# SP-PC-V3_0.net
KiCad netlist of a schematic drawn in EAGLE
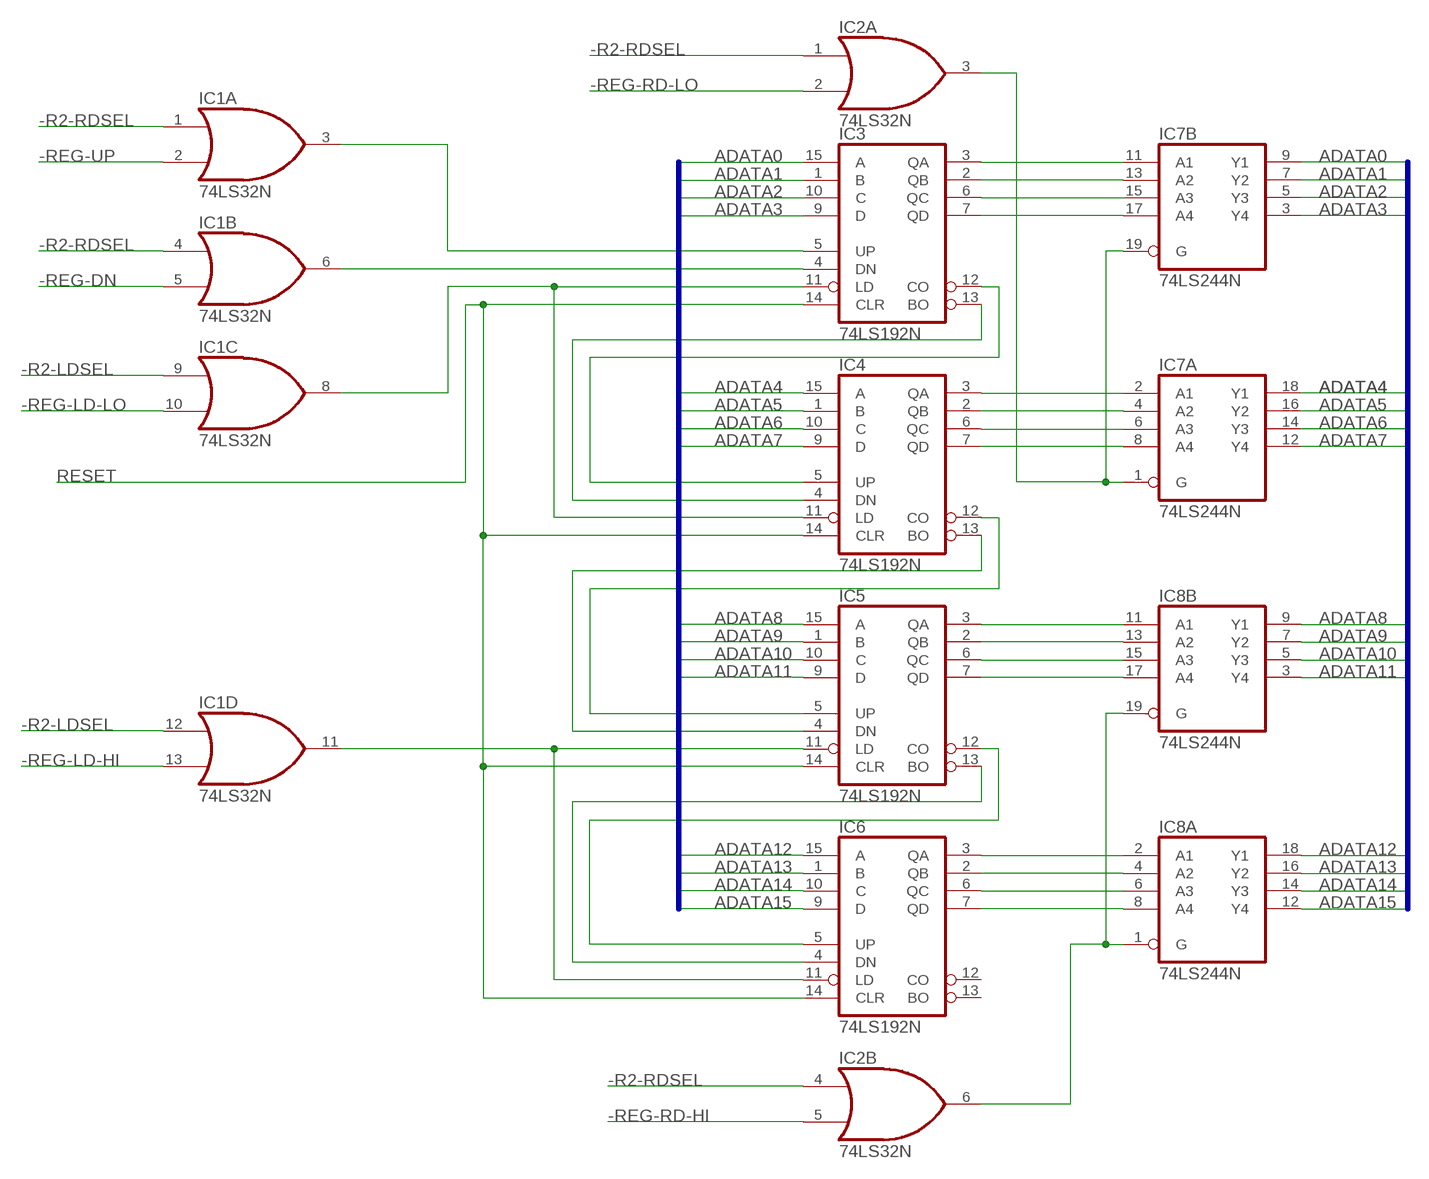
[diagram p0: schematic, sheet 1]
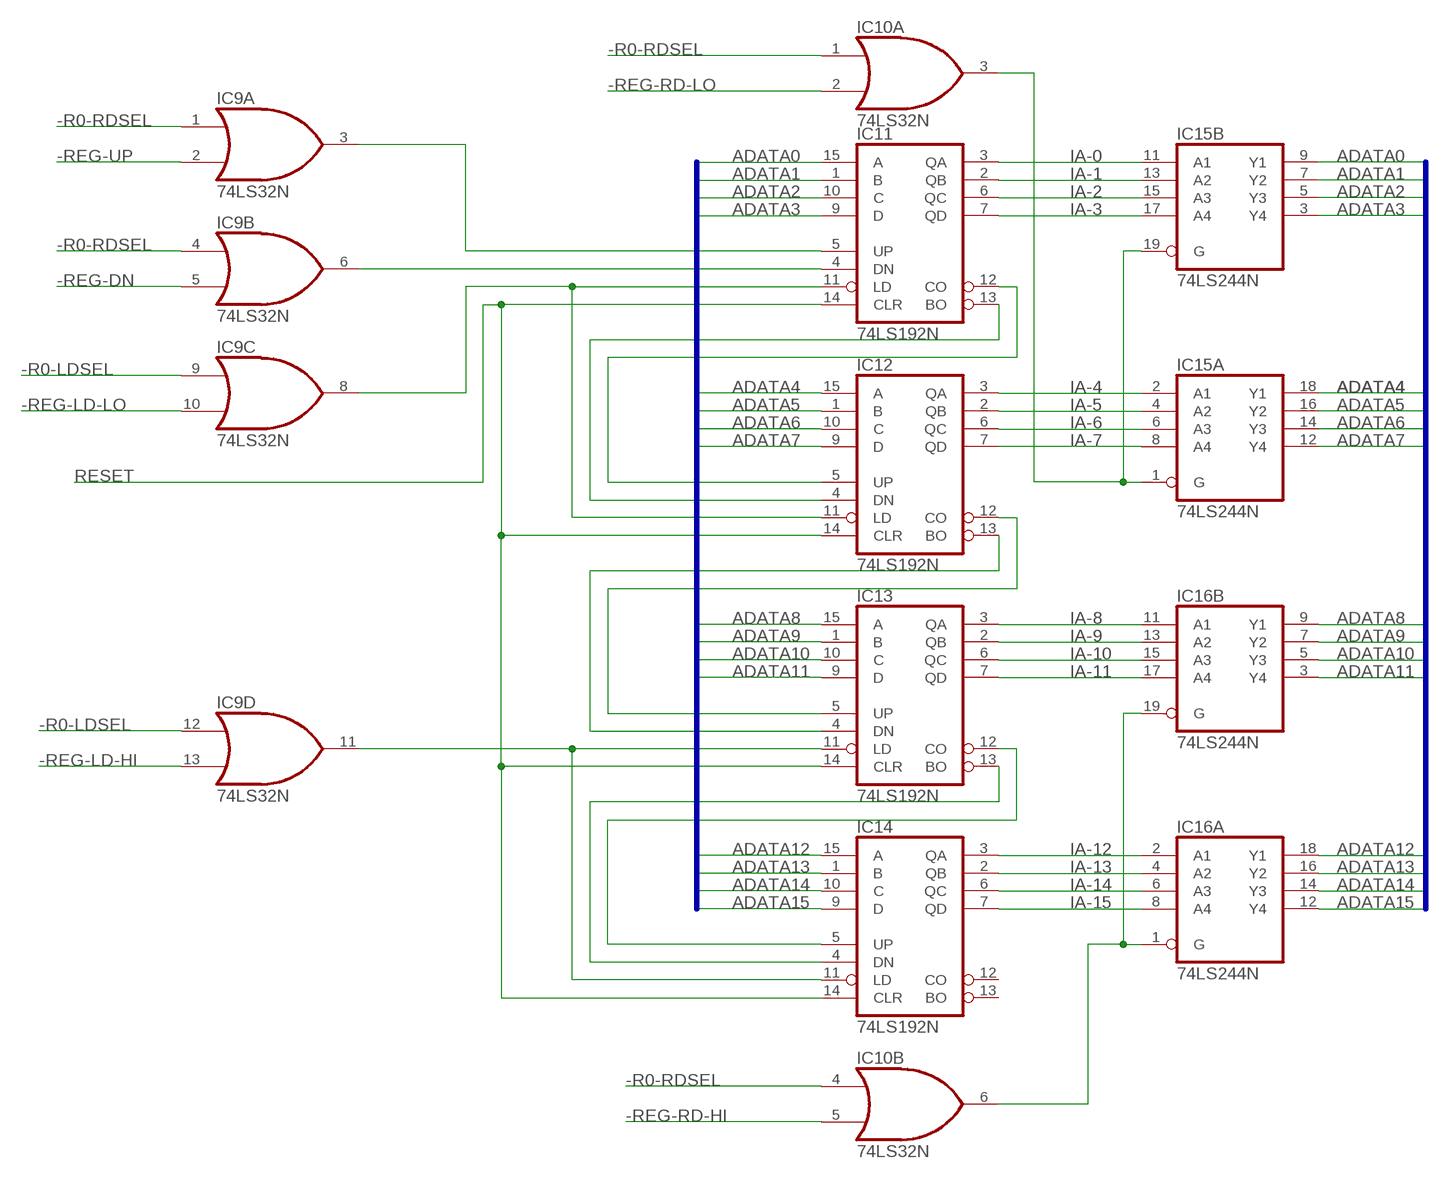
[diagram p1: schematic, sheet 2]
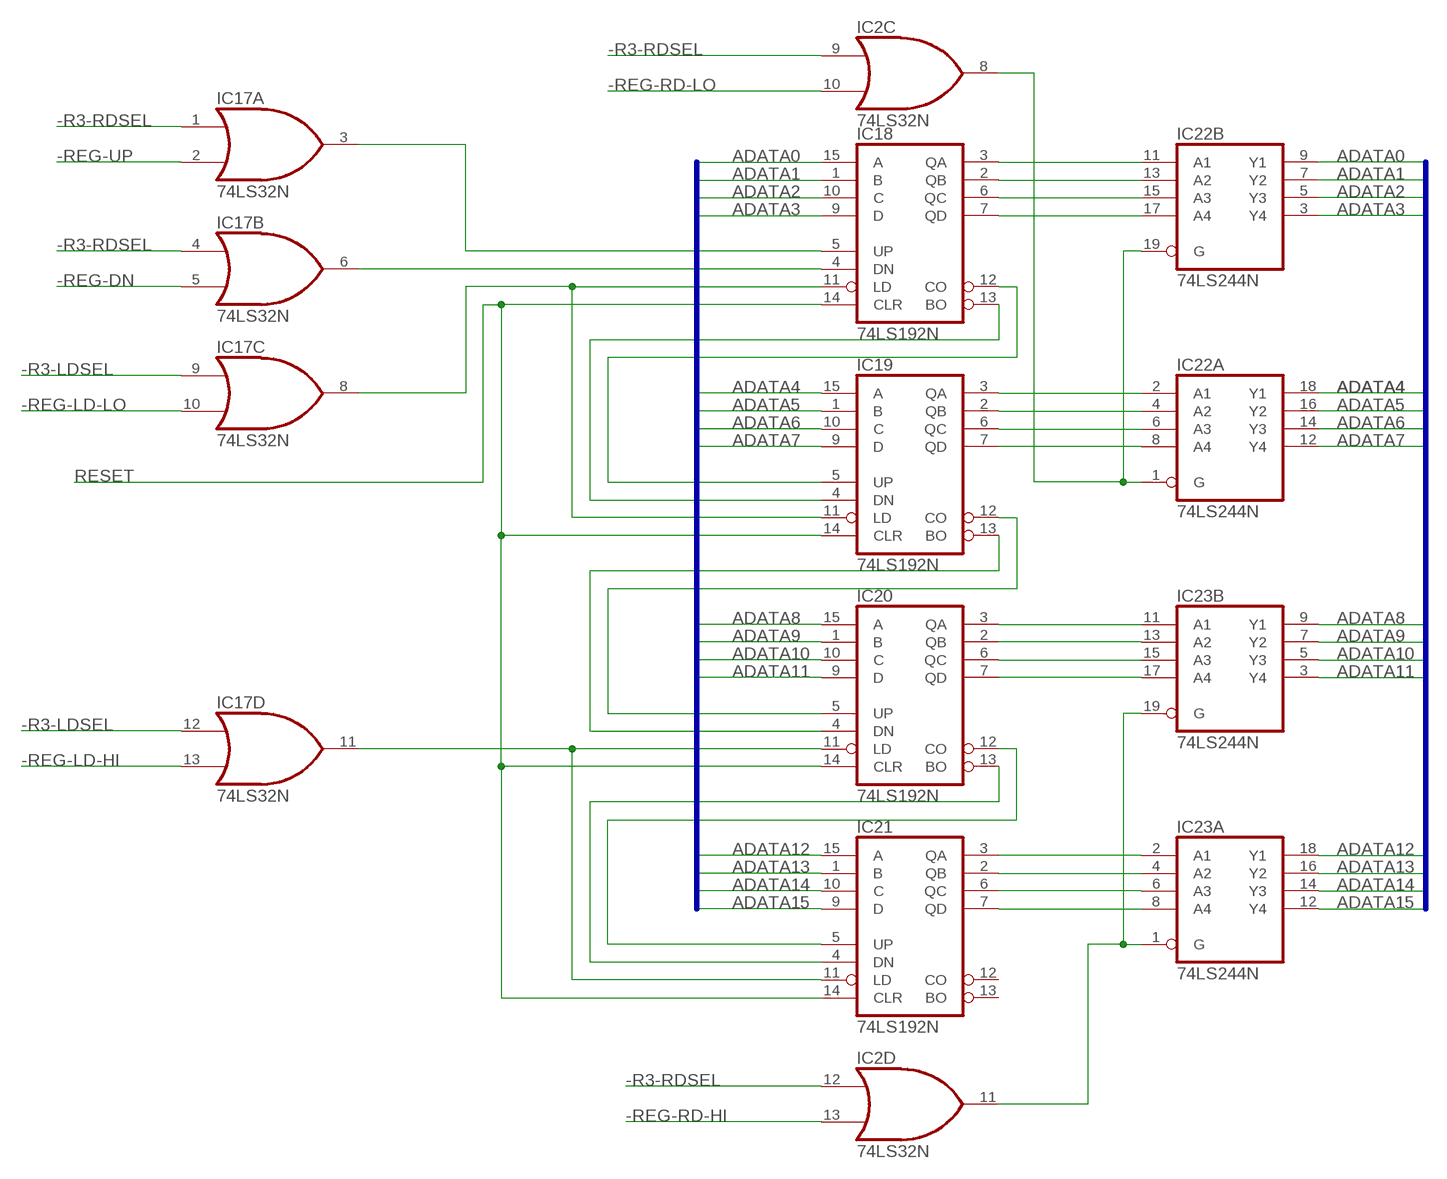
[diagram p2: schematic, sheet 3]
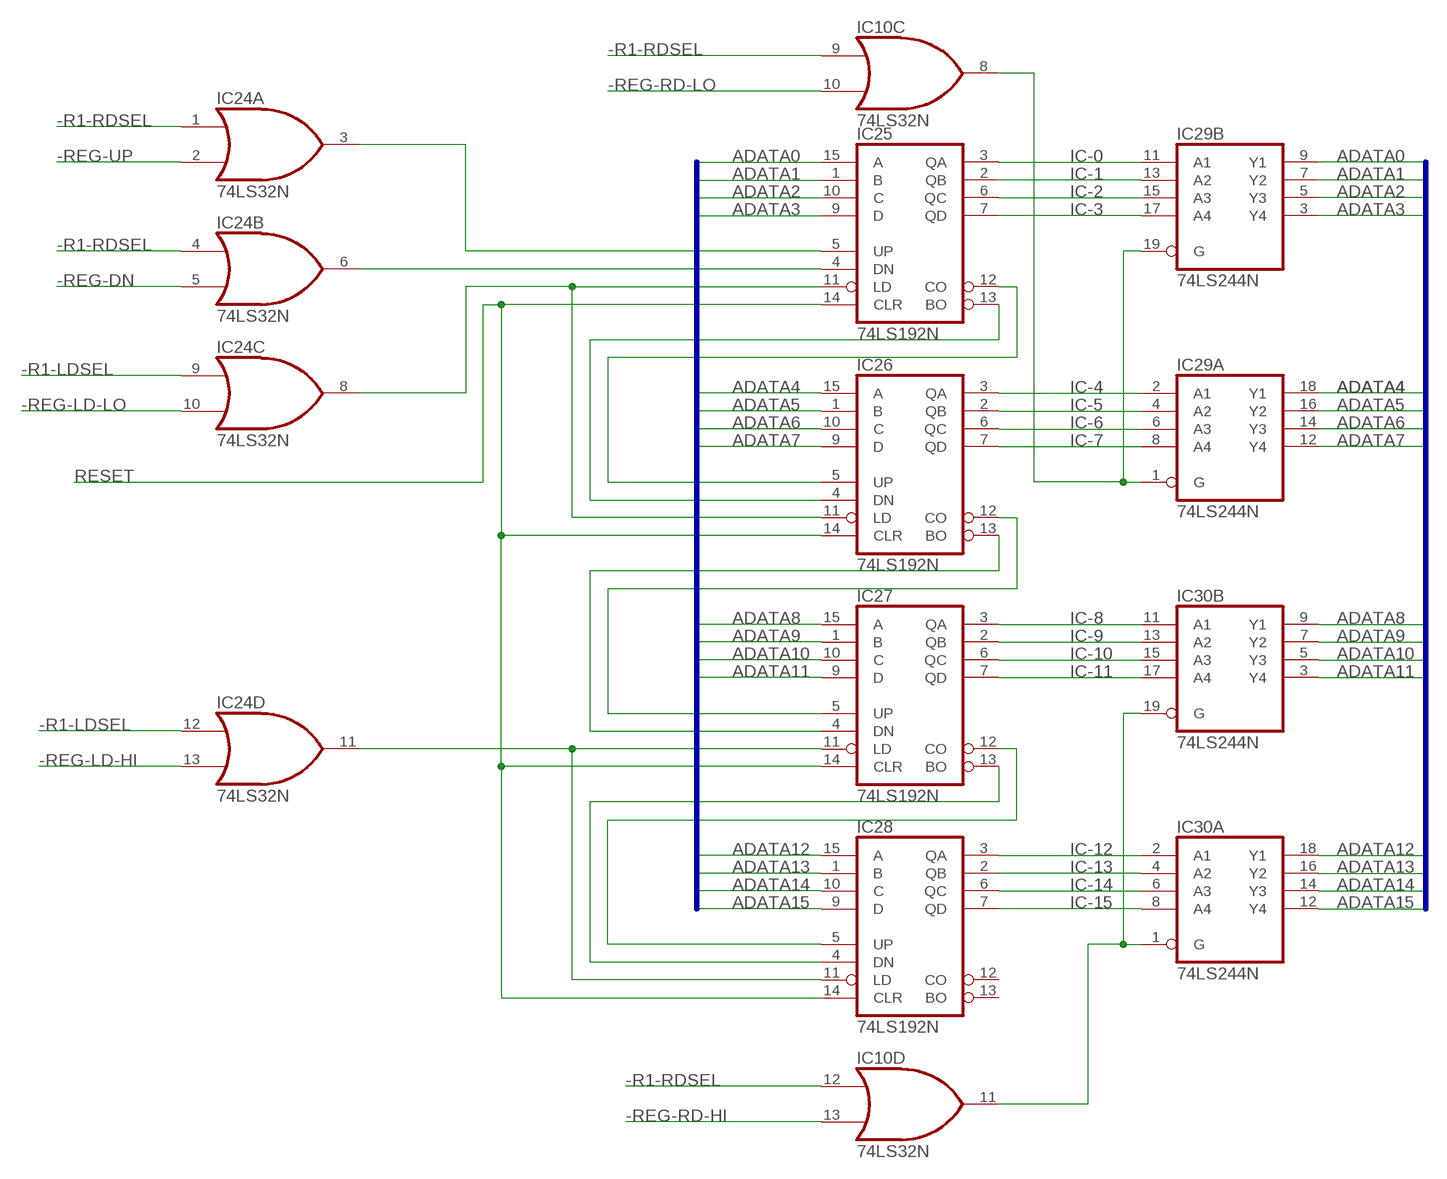
[diagram p3: schematic, sheet 4]
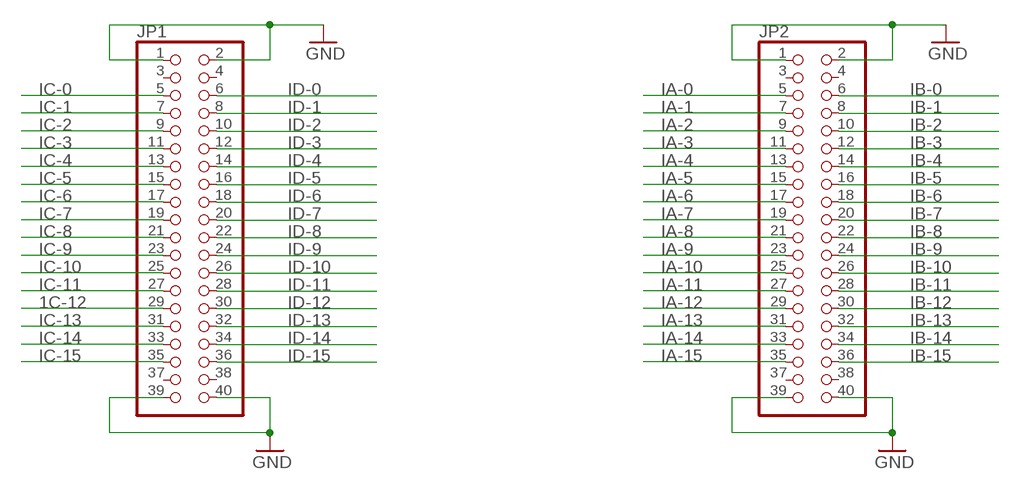
[diagram p4: schematic, sheet 5]
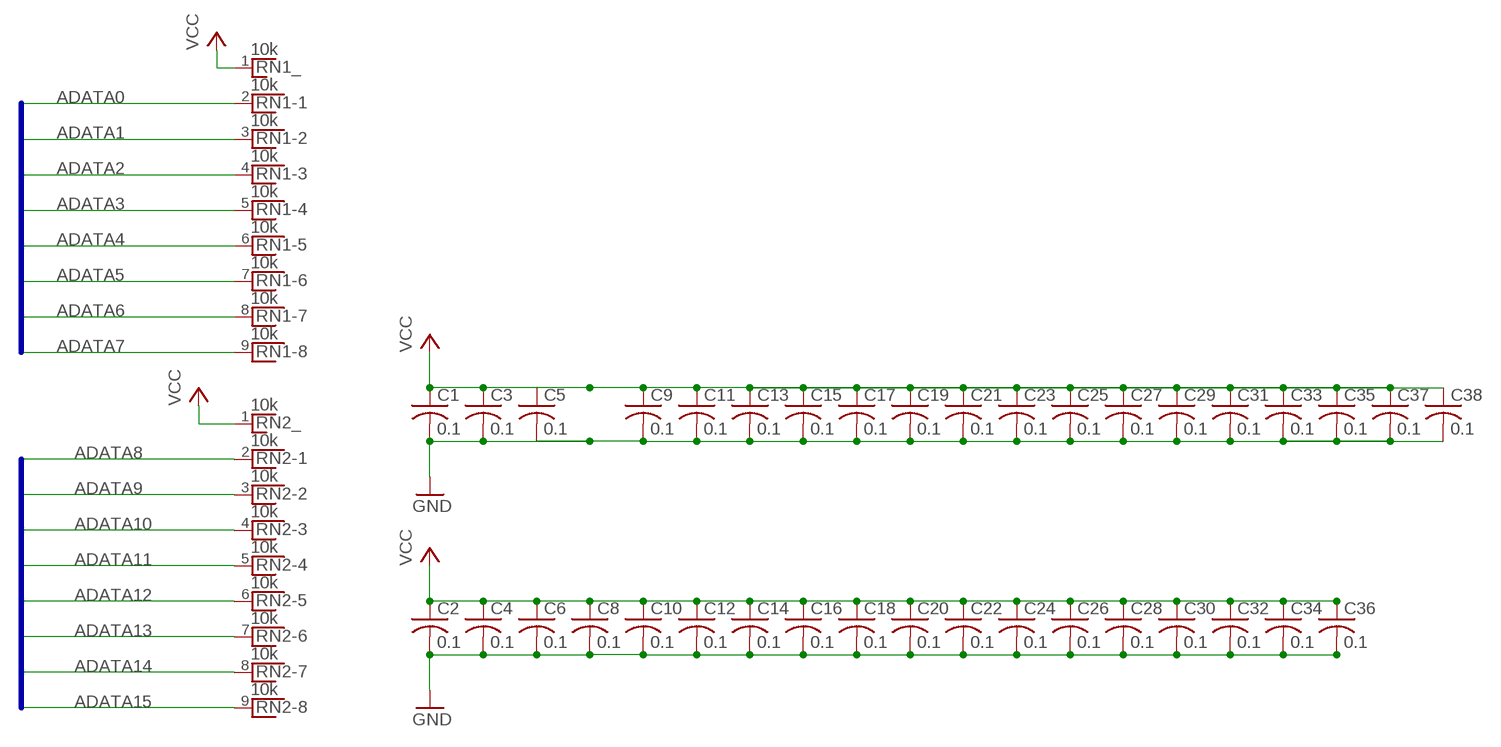
[diagram p5: schematic, sheet 6]
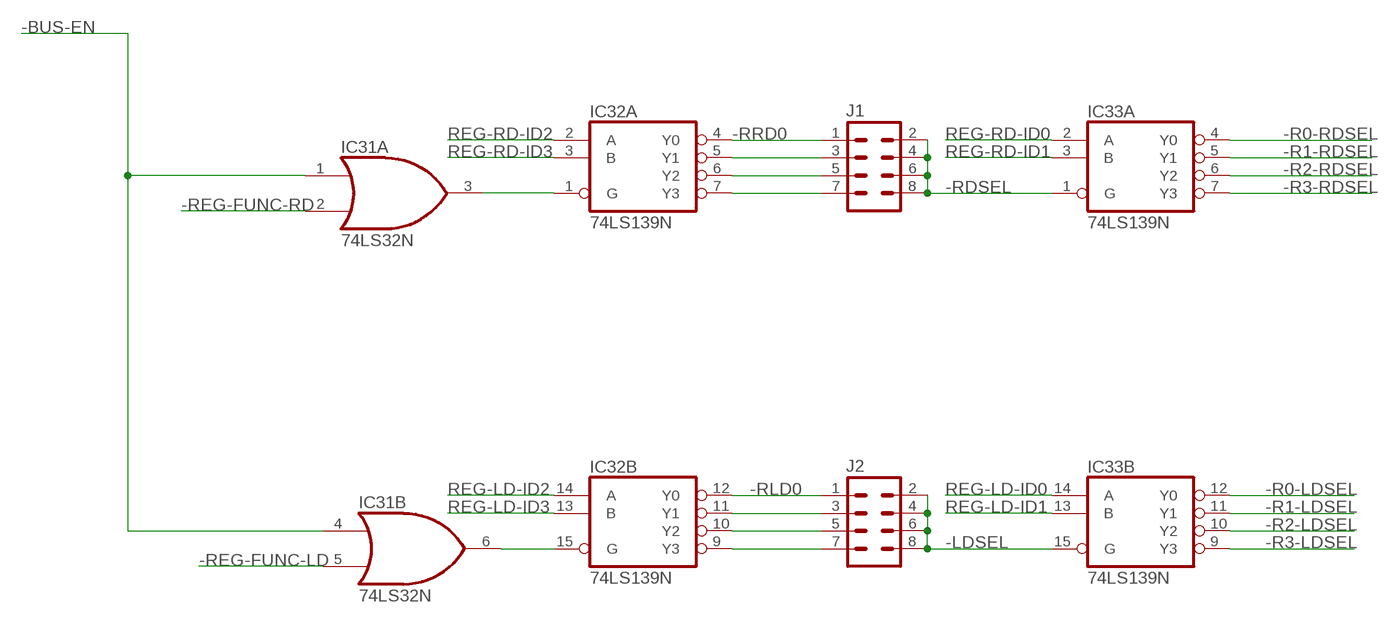
[diagram p6: schematic, sheet 7]
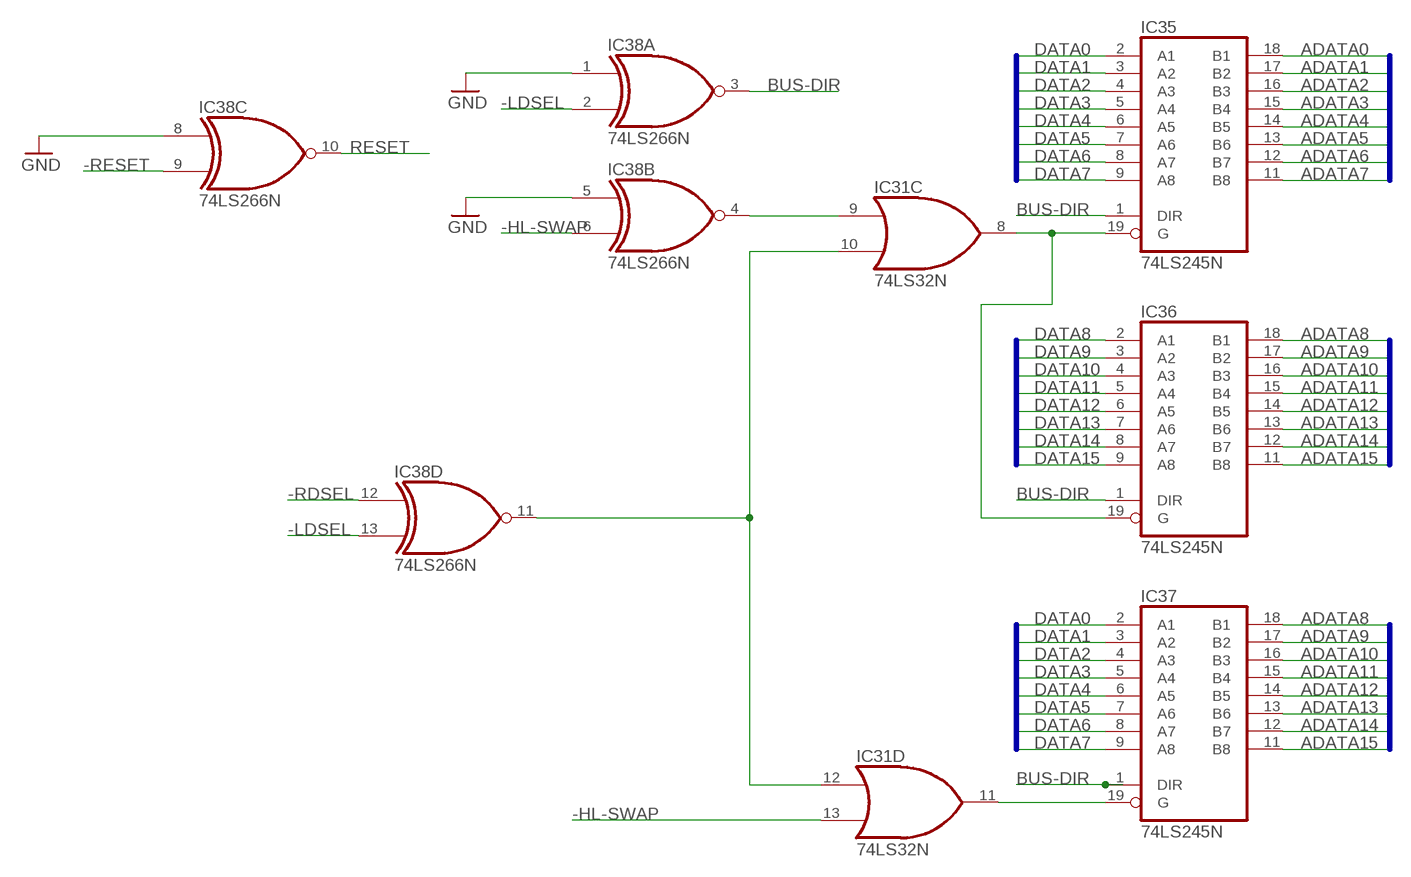
[diagram p7: schematic, sheet 8]
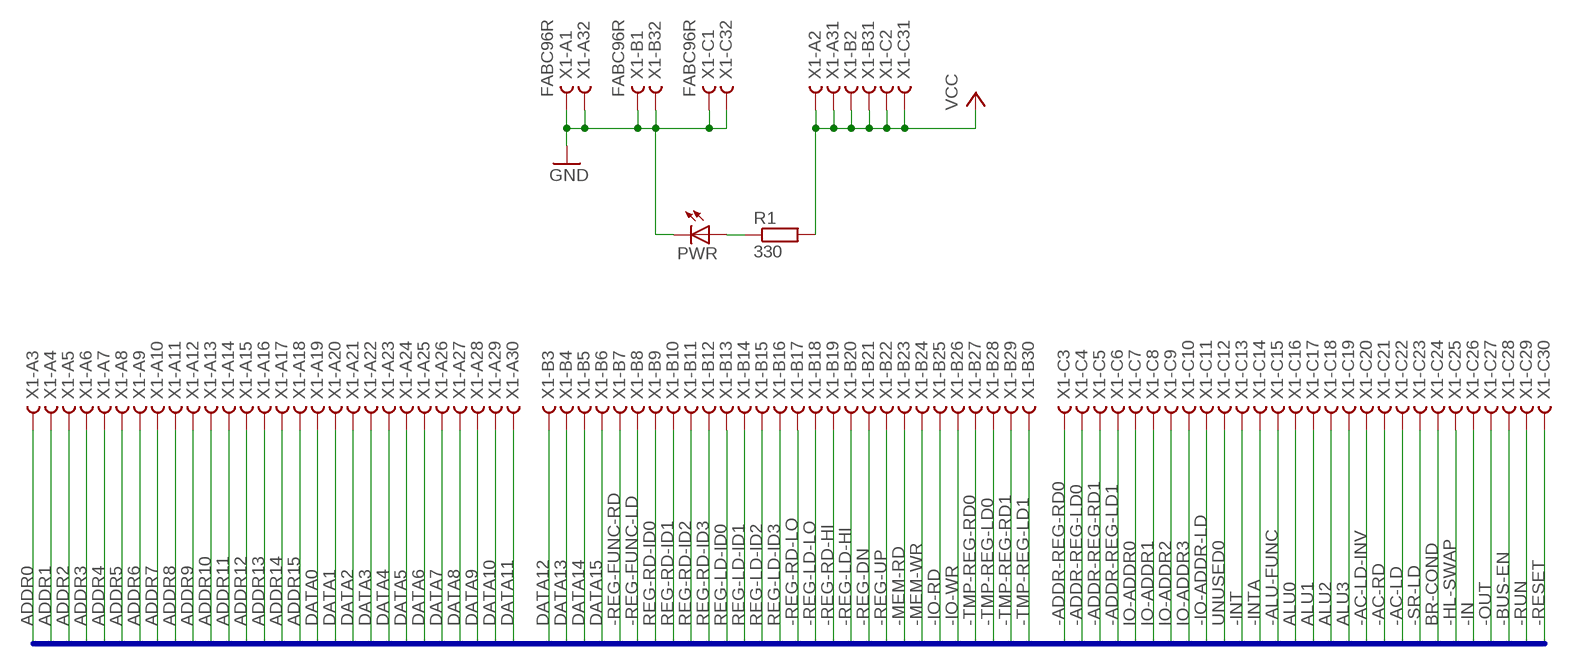
[diagram p8: schematic, sheet 9]

(export (version "E")
  (design (tool "Eeschema 10.0.6"))
  (components
    (comp (ref "IC31")
      (value "74LS32N")
      (footprint "eagle-import:DIL14")
      (libsource (lib "eagle-import") (part "7432NLS"))
    )
    (comp (ref "IC32")
      (value "74LS139N")
      (footprint "eagle-import:DIL16")
      (libsource (lib "eagle-import") (part "74139NLS"))
    )
    (comp (ref "IC33")
      (value "74LS139N")
      (footprint "eagle-import:DIL16")
      (libsource (lib "eagle-import") (part "74139NLS"))
    )
    (comp (ref "J1")
      (value "M04X2")
      (footprint "eagle-import:2X4")
      (libsource (lib "eagle-import") (part "M04X2"))
    )
    (comp (ref "J2")
      (value "M04X2")
      (footprint "eagle-import:2X4")
      (libsource (lib "eagle-import") (part "M04X2"))
    )
    (comp (ref "IC10")
      (value "74LS32N")
      (footprint "eagle-import:DIL14")
      (libsource (lib "eagle-import") (part "7432NLS"))
    )
    (comp (ref "IC24")
      (value "74LS32N")
      (footprint "eagle-import:DIL14")
      (libsource (lib "eagle-import") (part "7432NLS"))
    )
    (comp (ref "IC25")
      (value "74LS192N")
      (footprint "eagle-import:DIL16")
      (libsource (lib "eagle-import") (part "74192NLS"))
    )
    (comp (ref "IC26")
      (value "74LS192N")
      (footprint "eagle-import:DIL16")
      (libsource (lib "eagle-import") (part "74192NLS"))
    )
    (comp (ref "IC27")
      (value "74LS192N")
      (footprint "eagle-import:DIL16")
      (libsource (lib "eagle-import") (part "74192NLS"))
    )
    (comp (ref "IC28")
      (value "74LS192N")
      (footprint "eagle-import:DIL16")
      (libsource (lib "eagle-import") (part "74192NLS"))
    )
    (comp (ref "IC29")
      (value "74LS244N")
      (footprint "eagle-import:DIL20")
      (libsource (lib "eagle-import") (part "74xx-us_74244NLS"))
    )
    (comp (ref "IC30")
      (value "74LS244N")
      (footprint "eagle-import:DIL20")
      (libsource (lib "eagle-import") (part "74xx-us_74244NLS"))
    )
    (comp (ref "JP1")
      (value "PINHD-2X20")
      (footprint "eagle-import:2X20")
      (libsource (lib "eagle-import") (part "PINHD-2X20"))
    )
    (comp (ref "JP2")
      (value "PINHD-2X20")
      (footprint "eagle-import:2X20")
      (libsource (lib "eagle-import") (part "PINHD-2X20"))
    )
    (comp (ref "IC2")
      (value "74LS32N")
      (footprint "eagle-import:DIL14")
      (libsource (lib "eagle-import") (part "7432NLS"))
    )
    (comp (ref "IC17")
      (value "74LS32N")
      (footprint "eagle-import:DIL14")
      (libsource (lib "eagle-import") (part "7432NLS"))
    )
    (comp (ref "IC18")
      (value "74LS192N")
      (footprint "eagle-import:DIL16")
      (libsource (lib "eagle-import") (part "74192NLS"))
    )
    (comp (ref "IC19")
      (value "74LS192N")
      (footprint "eagle-import:DIL16")
      (libsource (lib "eagle-import") (part "74192NLS"))
    )
    (comp (ref "IC20")
      (value "74LS192N")
      (footprint "eagle-import:DIL16")
      (libsource (lib "eagle-import") (part "74192NLS"))
    )
    (comp (ref "IC21")
      (value "74LS192N")
      (footprint "eagle-import:DIL16")
      (libsource (lib "eagle-import") (part "74192NLS"))
    )
    (comp (ref "IC22")
      (value "74LS244N")
      (footprint "eagle-import:DIL20")
      (libsource (lib "eagle-import") (part "74xx-us_74244NLS"))
    )
    (comp (ref "IC23")
      (value "74LS244N")
      (footprint "eagle-import:DIL20")
      (libsource (lib "eagle-import") (part "74xx-us_74244NLS"))
    )
    (comp (ref "C1")
      (value "0.1")
      (footprint "eagle-import:C025-040X050")
      (libsource (lib "eagle-import") (part "C-US025-040X050"))
    )
    (comp (ref "C2")
      (value "0.1")
      (footprint "eagle-import:C025-040X050")
      (libsource (lib "eagle-import") (part "C-US025-040X050"))
    )
    (comp (ref "C3")
      (value "0.1")
      (footprint "eagle-import:C025-040X050")
      (libsource (lib "eagle-import") (part "C-US025-040X050"))
    )
    (comp (ref "C4")
      (value "0.1")
      (footprint "eagle-import:C025-040X050")
      (libsource (lib "eagle-import") (part "C-US025-040X050"))
    )
    (comp (ref "C5")
      (value "0.1")
      (footprint "eagle-import:C025-040X050")
      (libsource (lib "eagle-import") (part "C-US025-040X050"))
    )
    (comp (ref "C6")
      (value "0.1")
      (footprint "eagle-import:C025-040X050")
      (libsource (lib "eagle-import") (part "C-US025-040X050"))
    )
    (comp (ref "C8")
      (value "0.1")
      (footprint "eagle-import:C025-040X050")
      (libsource (lib "eagle-import") (part "C-US025-040X050"))
    )
    (comp (ref "C9")
      (value "0.1")
      (footprint "eagle-import:C025-040X050")
      (libsource (lib "eagle-import") (part "C-US025-040X050"))
    )
    (comp (ref "C10")
      (value "0.1")
      (footprint "eagle-import:C025-040X050")
      (libsource (lib "eagle-import") (part "C-US025-040X050"))
    )
    (comp (ref "C11")
      (value "0.1")
      (footprint "eagle-import:C025-040X050")
      (libsource (lib "eagle-import") (part "C-US025-040X050"))
    )
    (comp (ref "C12")
      (value "0.1")
      (footprint "eagle-import:C025-040X050")
      (libsource (lib "eagle-import") (part "C-US025-040X050"))
    )
    (comp (ref "C13")
      (value "0.1")
      (footprint "eagle-import:C025-040X050")
      (libsource (lib "eagle-import") (part "C-US025-040X050"))
    )
    (comp (ref "C14")
      (value "0.1")
      (footprint "eagle-import:C025-040X050")
      (libsource (lib "eagle-import") (part "C-US025-040X050"))
    )
    (comp (ref "C15")
      (value "0.1")
      (footprint "eagle-import:C025-040X050")
      (libsource (lib "eagle-import") (part "C-US025-040X050"))
    )
    (comp (ref "C16")
      (value "0.1")
      (footprint "eagle-import:C025-040X050")
      (libsource (lib "eagle-import") (part "C-US025-040X050"))
    )
    (comp (ref "C17")
      (value "0.1")
      (footprint "eagle-import:C025-040X050")
      (libsource (lib "eagle-import") (part "C-US025-040X050"))
    )
    (comp (ref "C18")
      (value "0.1")
      (footprint "eagle-import:C025-040X050")
      (libsource (lib "eagle-import") (part "C-US025-040X050"))
    )
    (comp (ref "C19")
      (value "0.1")
      (footprint "eagle-import:C025-040X050")
      (libsource (lib "eagle-import") (part "C-US025-040X050"))
    )
    (comp (ref "C20")
      (value "0.1")
      (footprint "eagle-import:C025-040X050")
      (libsource (lib "eagle-import") (part "C-US025-040X050"))
    )
    (comp (ref "C21")
      (value "0.1")
      (footprint "eagle-import:C025-040X050")
      (libsource (lib "eagle-import") (part "C-US025-040X050"))
    )
    (comp (ref "C22")
      (value "0.1")
      (footprint "eagle-import:C025-040X050")
      (libsource (lib "eagle-import") (part "C-US025-040X050"))
    )
    (comp (ref "C23")
      (value "0.1")
      (footprint "eagle-import:C025-040X050")
      (libsource (lib "eagle-import") (part "C-US025-040X050"))
    )
    (comp (ref "C24")
      (value "0.1")
      (footprint "eagle-import:C025-040X050")
      (libsource (lib "eagle-import") (part "C-US025-040X050"))
    )
    (comp (ref "C25")
      (value "0.1")
      (footprint "eagle-import:C025-040X050")
      (libsource (lib "eagle-import") (part "C-US025-040X050"))
    )
    (comp (ref "C26")
      (value "0.1")
      (footprint "eagle-import:C025-040X050")
      (libsource (lib "eagle-import") (part "C-US025-040X050"))
    )
    (comp (ref "C27")
      (value "0.1")
      (footprint "eagle-import:C025-040X050")
      (libsource (lib "eagle-import") (part "C-US025-040X050"))
    )
    (comp (ref "C28")
      (value "0.1")
      (footprint "eagle-import:C025-040X050")
      (libsource (lib "eagle-import") (part "C-US025-040X050"))
    )
    (comp (ref "C29")
      (value "0.1")
      (footprint "eagle-import:C025-040X050")
      (libsource (lib "eagle-import") (part "C-US025-040X050"))
    )
    (comp (ref "C30")
      (value "0.1")
      (footprint "eagle-import:C025-040X050")
      (libsource (lib "eagle-import") (part "C-US025-040X050"))
    )
    (comp (ref "C31")
      (value "0.1")
      (footprint "eagle-import:C025-040X050")
      (libsource (lib "eagle-import") (part "C-US025-040X050"))
    )
    (comp (ref "C32")
      (value "0.1")
      (footprint "eagle-import:C025-040X050")
      (libsource (lib "eagle-import") (part "C-US025-040X050"))
    )
    (comp (ref "C33")
      (value "0.1")
      (footprint "eagle-import:C025-040X050")
      (libsource (lib "eagle-import") (part "C-US025-040X050"))
    )
    (comp (ref "C34")
      (value "0.1")
      (footprint "eagle-import:C025-040X050")
      (libsource (lib "eagle-import") (part "C-US025-040X050"))
    )
    (comp (ref "C35")
      (value "0.1")
      (footprint "eagle-import:C025-040X050")
      (libsource (lib "eagle-import") (part "C-US025-040X050"))
    )
    (comp (ref "C36")
      (value "0.1")
      (footprint "eagle-import:C025-040X050")
      (libsource (lib "eagle-import") (part "C-US025-040X050"))
    )
    (comp (ref "C37")
      (value "0.1")
      (footprint "eagle-import:C025-040X050")
      (libsource (lib "eagle-import") (part "C-US025-040X050"))
    )
    (comp (ref "C38")
      (value "0.1")
      (footprint "eagle-import:C025-040X050")
      (libsource (lib "eagle-import") (part "C-US025-040X050"))
    )
    (comp (ref "RN1")
      (value "10k")
      (footprint "eagle-import:RN-9")
      (libsource (lib "eagle-import") (part "RNX8"))
    )
    (comp (ref "RN2")
      (value "10k")
      (footprint "eagle-import:RN-9")
      (libsource (lib "eagle-import") (part "RNX8"))
    )
    (comp (ref "IC35")
      (value "74LS245N")
      (footprint "eagle-import:DIL20")
      (libsource (lib "eagle-import") (part "74245NLS"))
    )
    (comp (ref "IC36")
      (value "74LS245N")
      (footprint "eagle-import:DIL20")
      (libsource (lib "eagle-import") (part "74245NLS"))
    )
    (comp (ref "IC37")
      (value "74LS245N")
      (footprint "eagle-import:DIL20")
      (libsource (lib "eagle-import") (part "74245NLS"))
    )
    (comp (ref "IC38")
      (value "74LS266N")
      (footprint "eagle-import:DIL14")
      (libsource (lib "eagle-import") (part "74266NLS"))
    )
    (comp (ref "PWR")
      (value "LED5MM")
      (footprint "eagle-import:LED5MM")
      (libsource (lib "eagle-import") (part "LED5MM"))
    )
    (comp (ref "R1")
      (value "330")
      (footprint "eagle-import:0207_10")
      (libsource (lib "eagle-import") (part "R0207/10"))
    )
    (comp (ref "X1")
      (value "FABC96R")
      (footprint "eagle-import:FABC96R")
      (libsource (lib "eagle-import") (part "FABC96R"))
    )
    (comp (ref "IC9")
      (value "74LS32N")
      (footprint "eagle-import:DIL14")
      (libsource (lib "eagle-import") (part "7432NLS"))
    )
    (comp (ref "IC11")
      (value "74LS192N")
      (footprint "eagle-import:DIL16")
      (libsource (lib "eagle-import") (part "74192NLS"))
    )
    (comp (ref "IC12")
      (value "74LS192N")
      (footprint "eagle-import:DIL16")
      (libsource (lib "eagle-import") (part "74192NLS"))
    )
    (comp (ref "IC13")
      (value "74LS192N")
      (footprint "eagle-import:DIL16")
      (libsource (lib "eagle-import") (part "74192NLS"))
    )
    (comp (ref "IC14")
      (value "74LS192N")
      (footprint "eagle-import:DIL16")
      (libsource (lib "eagle-import") (part "74192NLS"))
    )
    (comp (ref "IC15")
      (value "74LS244N")
      (footprint "eagle-import:DIL20")
      (libsource (lib "eagle-import") (part "74xx-us_74244NLS"))
    )
    (comp (ref "IC16")
      (value "74LS244N")
      (footprint "eagle-import:DIL20")
      (libsource (lib "eagle-import") (part "74xx-us_74244NLS"))
    )
    (comp (ref "IC1")
      (value "74LS32N")
      (footprint "eagle-import:DIL14")
      (libsource (lib "eagle-import") (part "7432NLS"))
    )
    (comp (ref "IC3")
      (value "74LS192N")
      (footprint "eagle-import:DIL16")
      (libsource (lib "eagle-import") (part "74192NLS"))
    )
    (comp (ref "IC4")
      (value "74LS192N")
      (footprint "eagle-import:DIL16")
      (libsource (lib "eagle-import") (part "74192NLS"))
    )
    (comp (ref "IC5")
      (value "74LS192N")
      (footprint "eagle-import:DIL16")
      (libsource (lib "eagle-import") (part "74192NLS"))
    )
    (comp (ref "IC6")
      (value "74LS192N")
      (footprint "eagle-import:DIL16")
      (libsource (lib "eagle-import") (part "74192NLS"))
    )
    (comp (ref "IC7")
      (value "74LS244N")
      (footprint "eagle-import:DIL20")
      (libsource (lib "eagle-import") (part "74xx-us_74244NLS"))
    )
    (comp (ref "IC8")
      (value "74LS244N")
      (footprint "eagle-import:DIL20")
      (libsource (lib "eagle-import") (part "74xx-us_74244NLS"))
    )
  )
  (nets
    (net (code "1") (name "-AC-LD") (class "Default")
      (node (ref "X1") (pin "C22") (pinfunction "B_C22") (pintype "passive"))
    )
    (net (code "2") (name "-AC-LD-INV") (class "Default")
      (node (ref "X1") (pin "C20") (pinfunction "B_C20") (pintype "passive"))
    )
    (net (code "3") (name "-AC-RD") (class "Default")
      (node (ref "X1") (pin "C21") (pinfunction "B_C21") (pintype "passive"))
    )
    (net (code "4") (name "-ADDR-REG-LD0") (class "Default")
      (node (ref "X1") (pin "C4") (pinfunction "B_C4") (pintype "passive"))
    )
    (net (code "5") (name "-ADDR-REG-LD1") (class "Default")
      (node (ref "X1") (pin "C6") (pinfunction "B_C6") (pintype "passive"))
    )
    (net (code "6") (name "-ADDR-REG-RD0") (class "Default")
      (node (ref "X1") (pin "C3") (pinfunction "B_C3") (pintype "passive"))
    )
    (net (code "7") (name "-ADDR-REG-RD1") (class "Default")
      (node (ref "X1") (pin "C5") (pinfunction "B_C5") (pintype "passive"))
    )
    (net (code "8") (name "-ALU-FUNC") (class "Default")
      (node (ref "X1") (pin "C15") (pinfunction "B_C15") (pintype "passive"))
    )
    (net (code "9") (name "-BUS-EN") (class "Default")
      (node (ref "IC31") (pin "1") (pinfunction "I0_1") (pintype "input"))
      (node (ref "IC31") (pin "4") (pinfunction "I0_4") (pintype "input"))
      (node (ref "X1") (pin "C28") (pinfunction "B_C28") (pintype "passive"))
    )
    (net (code "10") (name "-HL-SWAP") (class "Default")
      (node (ref "IC31") (pin "13") (pinfunction "I1_13") (pintype "input"))
      (node (ref "IC38") (pin "6") (pinfunction "I1_6") (pintype "input"))
      (node (ref "X1") (pin "C25") (pinfunction "B_C25") (pintype "passive"))
    )
    (net (code "11") (name "-IN") (class "Default")
      (node (ref "X1") (pin "C26") (pinfunction "B_C26") (pintype "passive"))
    )
    (net (code "12") (name "-INT") (class "Default")
      (node (ref "X1") (pin "C13") (pinfunction "B_C13") (pintype "passive"))
    )
    (net (code "13") (name "-INTA") (class "Default")
      (node (ref "X1") (pin "C14") (pinfunction "B_C14") (pintype "passive"))
    )
    (net (code "14") (name "-IO-ADDR-LD") (class "Default")
      (node (ref "X1") (pin "C11") (pinfunction "B_C11") (pintype "passive"))
    )
    (net (code "15") (name "-IO-RD") (class "Default")
      (node (ref "X1") (pin "B25") (pinfunction "B_B25") (pintype "passive"))
    )
    (net (code "16") (name "-IO-WR") (class "Default")
      (node (ref "X1") (pin "B26") (pinfunction "B_B26") (pintype "passive"))
    )
    (net (code "17") (name "-LDSEL") (class "Default")
      (node (ref "IC33") (pin "15") (pinfunction "G_15") (pintype "input"))
      (node (ref "IC38") (pin "13") (pinfunction "I1_13") (pintype "input"))
      (node (ref "IC38") (pin "2") (pinfunction "I1_2") (pintype "input"))
      (node (ref "J2") (pin "2") (pinfunction "2_2") (pintype "passive"))
      (node (ref "J2") (pin "4") (pinfunction "4_4") (pintype "passive"))
      (node (ref "J2") (pin "6") (pinfunction "6_6") (pintype "passive"))
      (node (ref "J2") (pin "8") (pinfunction "8_8") (pintype "passive"))
    )
    (net (code "18") (name "-MEM-RD") (class "Default")
      (node (ref "X1") (pin "B23") (pinfunction "B_B23") (pintype "passive"))
    )
    (net (code "19") (name "-MEM-WR") (class "Default")
      (node (ref "X1") (pin "B24") (pinfunction "B_B24") (pintype "passive"))
    )
    (net (code "20") (name "-OUT") (class "Default")
      (node (ref "X1") (pin "C27") (pinfunction "B_C27") (pintype "passive"))
    )
    (net (code "21") (name "-R0-LDSEL") (class "Default")
      (node (ref "IC33") (pin "12") (pinfunction "Y0_12") (pintype "output"))
      (node (ref "IC9") (pin "12") (pinfunction "I0_12") (pintype "input"))
      (node (ref "IC9") (pin "9") (pinfunction "I0_9") (pintype "input"))
    )
    (net (code "22") (name "-R0-RDSEL") (class "Default")
      (node (ref "IC10") (pin "1") (pinfunction "I0_1") (pintype "input"))
      (node (ref "IC10") (pin "4") (pinfunction "I0_4") (pintype "input"))
      (node (ref "IC33") (pin "4") (pinfunction "Y0_4") (pintype "output"))
      (node (ref "IC9") (pin "1") (pinfunction "I0_1") (pintype "input"))
      (node (ref "IC9") (pin "4") (pinfunction "I0_4") (pintype "input"))
    )
    (net (code "23") (name "-R1-LDSEL") (class "Default")
      (node (ref "IC24") (pin "12") (pinfunction "I0_12") (pintype "input"))
      (node (ref "IC24") (pin "9") (pinfunction "I0_9") (pintype "input"))
      (node (ref "IC33") (pin "11") (pinfunction "Y1_11") (pintype "output"))
    )
    (net (code "24") (name "-R1-RDSEL") (class "Default")
      (node (ref "IC10") (pin "12") (pinfunction "I0_12") (pintype "input"))
      (node (ref "IC10") (pin "9") (pinfunction "I0_9") (pintype "input"))
      (node (ref "IC24") (pin "1") (pinfunction "I0_1") (pintype "input"))
      (node (ref "IC24") (pin "4") (pinfunction "I0_4") (pintype "input"))
      (node (ref "IC33") (pin "5") (pinfunction "Y1_5") (pintype "output"))
    )
    (net (code "25") (name "-R2-LDSEL") (class "Default")
      (node (ref "IC1") (pin "12") (pinfunction "I0_12") (pintype "input"))
      (node (ref "IC1") (pin "9") (pinfunction "I0_9") (pintype "input"))
      (node (ref "IC33") (pin "10") (pinfunction "Y2_10") (pintype "output"))
    )
    (net (code "26") (name "-R2-RDSEL") (class "Default")
      (node (ref "IC1") (pin "1") (pinfunction "I0_1") (pintype "input"))
      (node (ref "IC1") (pin "4") (pinfunction "I0_4") (pintype "input"))
      (node (ref "IC2") (pin "1") (pinfunction "I0_1") (pintype "input"))
      (node (ref "IC2") (pin "4") (pinfunction "I0_4") (pintype "input"))
      (node (ref "IC33") (pin "6") (pinfunction "Y2_6") (pintype "output"))
    )
    (net (code "27") (name "-R3-LDSEL") (class "Default")
      (node (ref "IC17") (pin "12") (pinfunction "I0_12") (pintype "input"))
      (node (ref "IC17") (pin "9") (pinfunction "I0_9") (pintype "input"))
      (node (ref "IC33") (pin "9") (pinfunction "Y3_9") (pintype "output"))
    )
    (net (code "28") (name "-R3-RDSEL") (class "Default")
      (node (ref "IC17") (pin "1") (pinfunction "I0_1") (pintype "input"))
      (node (ref "IC17") (pin "4") (pinfunction "I0_4") (pintype "input"))
      (node (ref "IC2") (pin "12") (pinfunction "I0_12") (pintype "input"))
      (node (ref "IC2") (pin "9") (pinfunction "I0_9") (pintype "input"))
      (node (ref "IC33") (pin "7") (pinfunction "Y3_7") (pintype "output"))
    )
    (net (code "29") (name "-RDSEL") (class "Default")
      (node (ref "IC33") (pin "1") (pinfunction "G_1") (pintype "input"))
      (node (ref "IC38") (pin "12") (pinfunction "I0_12") (pintype "input"))
      (node (ref "J1") (pin "2") (pinfunction "2_2") (pintype "passive"))
      (node (ref "J1") (pin "4") (pinfunction "4_4") (pintype "passive"))
      (node (ref "J1") (pin "6") (pinfunction "6_6") (pintype "passive"))
      (node (ref "J1") (pin "8") (pinfunction "8_8") (pintype "passive"))
    )
    (net (code "30") (name "-REG-DN") (class "Default")
      (node (ref "IC1") (pin "5") (pinfunction "I1_5") (pintype "input"))
      (node (ref "IC17") (pin "5") (pinfunction "I1_5") (pintype "input"))
      (node (ref "IC24") (pin "5") (pinfunction "I1_5") (pintype "input"))
      (node (ref "IC9") (pin "5") (pinfunction "I1_5") (pintype "input"))
      (node (ref "X1") (pin "B21") (pinfunction "B_B21") (pintype "passive"))
    )
    (net (code "31") (name "-REG-FUNC-LD") (class "Default")
      (node (ref "IC31") (pin "5") (pinfunction "I1_5") (pintype "input"))
      (node (ref "X1") (pin "B8") (pinfunction "B_B8") (pintype "passive"))
    )
    (net (code "32") (name "-REG-FUNC-RD") (class "Default")
      (node (ref "IC31") (pin "2") (pinfunction "I1_2") (pintype "input"))
      (node (ref "X1") (pin "B7") (pinfunction "B_B7") (pintype "passive"))
    )
    (net (code "33") (name "-REG-LD-HI") (class "Default")
      (node (ref "IC1") (pin "13") (pinfunction "I1_13") (pintype "input"))
      (node (ref "IC17") (pin "13") (pinfunction "I1_13") (pintype "input"))
      (node (ref "IC24") (pin "13") (pinfunction "I1_13") (pintype "input"))
      (node (ref "IC9") (pin "13") (pinfunction "I1_13") (pintype "input"))
      (node (ref "X1") (pin "B20") (pinfunction "B_B20") (pintype "passive"))
    )
    (net (code "34") (name "-REG-LD-LO") (class "Default")
      (node (ref "IC1") (pin "10") (pinfunction "I1_10") (pintype "input"))
      (node (ref "IC17") (pin "10") (pinfunction "I1_10") (pintype "input"))
      (node (ref "IC24") (pin "10") (pinfunction "I1_10") (pintype "input"))
      (node (ref "IC9") (pin "10") (pinfunction "I1_10") (pintype "input"))
      (node (ref "X1") (pin "B18") (pinfunction "B_B18") (pintype "passive"))
    )
    (net (code "35") (name "-REG-RD-HI") (class "Default")
      (node (ref "IC10") (pin "13") (pinfunction "I1_13") (pintype "input"))
      (node (ref "IC10") (pin "5") (pinfunction "I1_5") (pintype "input"))
      (node (ref "IC2") (pin "13") (pinfunction "I1_13") (pintype "input"))
      (node (ref "IC2") (pin "5") (pinfunction "I1_5") (pintype "input"))
      (node (ref "X1") (pin "B19") (pinfunction "B_B19") (pintype "passive"))
    )
    (net (code "36") (name "-REG-RD-LO") (class "Default")
      (node (ref "IC10") (pin "10") (pinfunction "I1_10") (pintype "input"))
      (node (ref "IC10") (pin "2") (pinfunction "I1_2") (pintype "input"))
      (node (ref "IC2") (pin "10") (pinfunction "I1_10") (pintype "input"))
      (node (ref "IC2") (pin "2") (pinfunction "I1_2") (pintype "input"))
      (node (ref "X1") (pin "B17") (pinfunction "B_B17") (pintype "passive"))
    )
    (net (code "37") (name "-REG-UP") (class "Default")
      (node (ref "IC1") (pin "2") (pinfunction "I1_2") (pintype "input"))
      (node (ref "IC17") (pin "2") (pinfunction "I1_2") (pintype "input"))
      (node (ref "IC24") (pin "2") (pinfunction "I1_2") (pintype "input"))
      (node (ref "IC9") (pin "2") (pinfunction "I1_2") (pintype "input"))
      (node (ref "X1") (pin "B22") (pinfunction "B_B22") (pintype "passive"))
    )
    (net (code "38") (name "-RESET") (class "Default")
      (node (ref "IC38") (pin "9") (pinfunction "I1_9") (pintype "input"))
      (node (ref "X1") (pin "C30") (pinfunction "B_C30") (pintype "passive"))
    )
    (net (code "39") (name "-RLD0") (class "Default")
      (node (ref "IC32") (pin "12") (pinfunction "Y0_12") (pintype "output"))
      (node (ref "J2") (pin "1") (pinfunction "1_1") (pintype "passive"))
    )
    (net (code "40") (name "-RRD0") (class "Default")
      (node (ref "IC32") (pin "4") (pinfunction "Y0_4") (pintype "output"))
      (node (ref "J1") (pin "1") (pinfunction "1_1") (pintype "passive"))
    )
    (net (code "41") (name "-RUN") (class "Default")
      (node (ref "X1") (pin "C29") (pinfunction "B_C29") (pintype "passive"))
    )
    (net (code "42") (name "-SR-LD") (class "Default")
      (node (ref "X1") (pin "C23") (pinfunction "B_C23") (pintype "passive"))
    )
    (net (code "43") (name "-TMP-REG-LD0") (class "Default")
      (node (ref "X1") (pin "B28") (pinfunction "B_B28") (pintype "passive"))
    )
    (net (code "44") (name "-TMP-REG-LD1") (class "Default")
      (node (ref "X1") (pin "B30") (pinfunction "B_B30") (pintype "passive"))
    )
    (net (code "45") (name "-TMP-REG-RD0") (class "Default")
      (node (ref "X1") (pin "B27") (pinfunction "B_B27") (pintype "passive"))
    )
    (net (code "46") (name "-TMP-REG-RD1") (class "Default")
      (node (ref "X1") (pin "B29") (pinfunction "B_B29") (pintype "passive"))
    )
    (net (code "47") (name "1C-12") (class "Default")
      (node (ref "JP1") (pin "29") (pinfunction "29_29") (pintype "passive"))
    )
    (net (code "48") (name "ADATA0") (class "Default")
      (node (ref "IC11") (pin "15") (pinfunction "A_15") (pintype "input"))
      (node (ref "IC15") (pin "9") (pinfunction "Y1_9") (pintype "tri_state"))
      (node (ref "IC18") (pin "15") (pinfunction "A_15") (pintype "input"))
      (node (ref "IC22") (pin "9") (pinfunction "Y1_9") (pintype "tri_state"))
      (node (ref "IC25") (pin "15") (pinfunction "A_15") (pintype "input"))
      (node (ref "IC29") (pin "9") (pinfunction "Y1_9") (pintype "tri_state"))
      (node (ref "IC3") (pin "15") (pinfunction "A_15") (pintype "input"))
      (node (ref "IC35") (pin "18") (pinfunction "B1_18") (pintype "bidirectional"))
      (node (ref "IC7") (pin "9") (pinfunction "Y1_9") (pintype "tri_state"))
      (node (ref "RN1") (pin "2") (pinfunction "1_2") (pintype "passive"))
    )
    (net (code "49") (name "ADATA1") (class "Default")
      (node (ref "IC11") (pin "1") (pinfunction "B_1") (pintype "input"))
      (node (ref "IC15") (pin "7") (pinfunction "Y2_7") (pintype "tri_state"))
      (node (ref "IC18") (pin "1") (pinfunction "B_1") (pintype "input"))
      (node (ref "IC22") (pin "7") (pinfunction "Y2_7") (pintype "tri_state"))
      (node (ref "IC25") (pin "1") (pinfunction "B_1") (pintype "input"))
      (node (ref "IC29") (pin "7") (pinfunction "Y2_7") (pintype "tri_state"))
      (node (ref "IC3") (pin "1") (pinfunction "B_1") (pintype "input"))
      (node (ref "IC35") (pin "17") (pinfunction "B2_17") (pintype "bidirectional"))
      (node (ref "IC7") (pin "7") (pinfunction "Y2_7") (pintype "tri_state"))
      (node (ref "RN1") (pin "3") (pinfunction "1_3") (pintype "passive"))
    )
    (net (code "50") (name "ADATA2") (class "Default")
      (node (ref "IC11") (pin "10") (pinfunction "C_10") (pintype "input"))
      (node (ref "IC15") (pin "5") (pinfunction "Y3_5") (pintype "tri_state"))
      (node (ref "IC18") (pin "10") (pinfunction "C_10") (pintype "input"))
      (node (ref "IC22") (pin "5") (pinfunction "Y3_5") (pintype "tri_state"))
      (node (ref "IC25") (pin "10") (pinfunction "C_10") (pintype "input"))
      (node (ref "IC29") (pin "5") (pinfunction "Y3_5") (pintype "tri_state"))
      (node (ref "IC3") (pin "10") (pinfunction "C_10") (pintype "input"))
      (node (ref "IC35") (pin "16") (pinfunction "B3_16") (pintype "bidirectional"))
      (node (ref "IC7") (pin "5") (pinfunction "Y3_5") (pintype "tri_state"))
      (node (ref "RN1") (pin "4") (pinfunction "1_4") (pintype "passive"))
    )
    (net (code "51") (name "ADATA3") (class "Default")
      (node (ref "IC11") (pin "9") (pinfunction "D_9") (pintype "input"))
      (node (ref "IC15") (pin "3") (pinfunction "Y4_3") (pintype "tri_state"))
      (node (ref "IC18") (pin "9") (pinfunction "D_9") (pintype "input"))
      (node (ref "IC22") (pin "3") (pinfunction "Y4_3") (pintype "tri_state"))
      (node (ref "IC25") (pin "9") (pinfunction "D_9") (pintype "input"))
      (node (ref "IC29") (pin "3") (pinfunction "Y4_3") (pintype "tri_state"))
      (node (ref "IC3") (pin "9") (pinfunction "D_9") (pintype "input"))
      (node (ref "IC35") (pin "15") (pinfunction "B4_15") (pintype "bidirectional"))
      (node (ref "IC7") (pin "3") (pinfunction "Y4_3") (pintype "tri_state"))
      (node (ref "RN1") (pin "5") (pinfunction "1_5") (pintype "passive"))
    )
    (net (code "52") (name "ADATA4") (class "Default")
      (node (ref "IC12") (pin "15") (pinfunction "A_15") (pintype "input"))
      (node (ref "IC15") (pin "18") (pinfunction "Y1_18") (pintype "tri_state"))
      (node (ref "IC19") (pin "15") (pinfunction "A_15") (pintype "input"))
      (node (ref "IC22") (pin "18") (pinfunction "Y1_18") (pintype "tri_state"))
      (node (ref "IC26") (pin "15") (pinfunction "A_15") (pintype "input"))
      (node (ref "IC29") (pin "18") (pinfunction "Y1_18") (pintype "tri_state"))
      (node (ref "IC35") (pin "14") (pinfunction "B5_14") (pintype "bidirectional"))
      (node (ref "IC4") (pin "15") (pinfunction "A_15") (pintype "input"))
      (node (ref "IC7") (pin "18") (pinfunction "Y1_18") (pintype "tri_state"))
      (node (ref "RN1") (pin "6") (pinfunction "1_6") (pintype "passive"))
    )
    (net (code "53") (name "ADATA5") (class "Default")
      (node (ref "IC12") (pin "1") (pinfunction "B_1") (pintype "input"))
      (node (ref "IC15") (pin "16") (pinfunction "Y2_16") (pintype "tri_state"))
      (node (ref "IC19") (pin "1") (pinfunction "B_1") (pintype "input"))
      (node (ref "IC22") (pin "16") (pinfunction "Y2_16") (pintype "tri_state"))
      (node (ref "IC26") (pin "1") (pinfunction "B_1") (pintype "input"))
      (node (ref "IC29") (pin "16") (pinfunction "Y2_16") (pintype "tri_state"))
      (node (ref "IC35") (pin "13") (pinfunction "B6_13") (pintype "bidirectional"))
      (node (ref "IC4") (pin "1") (pinfunction "B_1") (pintype "input"))
      (node (ref "IC7") (pin "16") (pinfunction "Y2_16") (pintype "tri_state"))
      (node (ref "RN1") (pin "7") (pinfunction "1_7") (pintype "passive"))
    )
    (net (code "54") (name "ADATA6") (class "Default")
      (node (ref "IC12") (pin "10") (pinfunction "C_10") (pintype "input"))
      (node (ref "IC15") (pin "14") (pinfunction "Y3_14") (pintype "tri_state"))
      (node (ref "IC19") (pin "10") (pinfunction "C_10") (pintype "input"))
      (node (ref "IC22") (pin "14") (pinfunction "Y3_14") (pintype "tri_state"))
      (node (ref "IC26") (pin "10") (pinfunction "C_10") (pintype "input"))
      (node (ref "IC29") (pin "14") (pinfunction "Y3_14") (pintype "tri_state"))
      (node (ref "IC35") (pin "12") (pinfunction "B7_12") (pintype "bidirectional"))
      (node (ref "IC4") (pin "10") (pinfunction "C_10") (pintype "input"))
      (node (ref "IC7") (pin "14") (pinfunction "Y3_14") (pintype "tri_state"))
      (node (ref "RN1") (pin "8") (pinfunction "1_8") (pintype "passive"))
    )
    (net (code "55") (name "ADATA7") (class "Default")
      (node (ref "IC12") (pin "9") (pinfunction "D_9") (pintype "input"))
      (node (ref "IC15") (pin "12") (pinfunction "Y4_12") (pintype "tri_state"))
      (node (ref "IC19") (pin "9") (pinfunction "D_9") (pintype "input"))
      (node (ref "IC22") (pin "12") (pinfunction "Y4_12") (pintype "tri_state"))
      (node (ref "IC26") (pin "9") (pinfunction "D_9") (pintype "input"))
      (node (ref "IC29") (pin "12") (pinfunction "Y4_12") (pintype "tri_state"))
      (node (ref "IC35") (pin "11") (pinfunction "B8_11") (pintype "bidirectional"))
      (node (ref "IC4") (pin "9") (pinfunction "D_9") (pintype "input"))
      (node (ref "IC7") (pin "12") (pinfunction "Y4_12") (pintype "tri_state"))
      (node (ref "RN1") (pin "9") (pinfunction "1_9") (pintype "passive"))
    )
    (net (code "56") (name "ADATA8") (class "Default")
      (node (ref "IC13") (pin "15") (pinfunction "A_15") (pintype "input"))
      (node (ref "IC16") (pin "9") (pinfunction "Y1_9") (pintype "tri_state"))
      (node (ref "IC20") (pin "15") (pinfunction "A_15") (pintype "input"))
      (node (ref "IC23") (pin "9") (pinfunction "Y1_9") (pintype "tri_state"))
      (node (ref "IC27") (pin "15") (pinfunction "A_15") (pintype "input"))
      (node (ref "IC30") (pin "9") (pinfunction "Y1_9") (pintype "tri_state"))
      (node (ref "IC36") (pin "18") (pinfunction "B1_18") (pintype "bidirectional"))
      (node (ref "IC37") (pin "18") (pinfunction "B1_18") (pintype "bidirectional"))
      (node (ref "IC5") (pin "15") (pinfunction "A_15") (pintype "input"))
      (node (ref "IC8") (pin "9") (pinfunction "Y1_9") (pintype "tri_state"))
      (node (ref "RN2") (pin "2") (pinfunction "1_2") (pintype "passive"))
    )
    (net (code "57") (name "ADATA9") (class "Default")
      (node (ref "IC13") (pin "1") (pinfunction "B_1") (pintype "input"))
      (node (ref "IC16") (pin "7") (pinfunction "Y2_7") (pintype "tri_state"))
      (node (ref "IC20") (pin "1") (pinfunction "B_1") (pintype "input"))
      (node (ref "IC23") (pin "7") (pinfunction "Y2_7") (pintype "tri_state"))
      (node (ref "IC27") (pin "1") (pinfunction "B_1") (pintype "input"))
      (node (ref "IC30") (pin "7") (pinfunction "Y2_7") (pintype "tri_state"))
      (node (ref "IC36") (pin "17") (pinfunction "B2_17") (pintype "bidirectional"))
      (node (ref "IC37") (pin "17") (pinfunction "B2_17") (pintype "bidirectional"))
      (node (ref "IC5") (pin "1") (pinfunction "B_1") (pintype "input"))
      (node (ref "IC8") (pin "7") (pinfunction "Y2_7") (pintype "tri_state"))
      (node (ref "RN2") (pin "3") (pinfunction "1_3") (pintype "passive"))
    )
    (net (code "58") (name "ADATA10") (class "Default")
      (node (ref "IC13") (pin "10") (pinfunction "C_10") (pintype "input"))
      (node (ref "IC16") (pin "5") (pinfunction "Y3_5") (pintype "tri_state"))
      (node (ref "IC20") (pin "10") (pinfunction "C_10") (pintype "input"))
      (node (ref "IC23") (pin "5") (pinfunction "Y3_5") (pintype "tri_state"))
      (node (ref "IC27") (pin "10") (pinfunction "C_10") (pintype "input"))
      (node (ref "IC30") (pin "5") (pinfunction "Y3_5") (pintype "tri_state"))
      (node (ref "IC36") (pin "16") (pinfunction "B3_16") (pintype "bidirectional"))
      (node (ref "IC37") (pin "16") (pinfunction "B3_16") (pintype "bidirectional"))
      (node (ref "IC5") (pin "10") (pinfunction "C_10") (pintype "input"))
      (node (ref "IC8") (pin "5") (pinfunction "Y3_5") (pintype "tri_state"))
      (node (ref "RN2") (pin "4") (pinfunction "1_4") (pintype "passive"))
    )
    (net (code "59") (name "ADATA11") (class "Default")
      (node (ref "IC13") (pin "9") (pinfunction "D_9") (pintype "input"))
      (node (ref "IC16") (pin "3") (pinfunction "Y4_3") (pintype "tri_state"))
      (node (ref "IC20") (pin "9") (pinfunction "D_9") (pintype "input"))
      (node (ref "IC23") (pin "3") (pinfunction "Y4_3") (pintype "tri_state"))
      (node (ref "IC27") (pin "9") (pinfunction "D_9") (pintype "input"))
      (node (ref "IC30") (pin "3") (pinfunction "Y4_3") (pintype "tri_state"))
      (node (ref "IC36") (pin "15") (pinfunction "B4_15") (pintype "bidirectional"))
      (node (ref "IC37") (pin "15") (pinfunction "B4_15") (pintype "bidirectional"))
      (node (ref "IC5") (pin "9") (pinfunction "D_9") (pintype "input"))
      (node (ref "IC8") (pin "3") (pinfunction "Y4_3") (pintype "tri_state"))
      (node (ref "RN2") (pin "5") (pinfunction "1_5") (pintype "passive"))
    )
    (net (code "60") (name "ADATA12") (class "Default")
      (node (ref "IC14") (pin "15") (pinfunction "A_15") (pintype "input"))
      (node (ref "IC16") (pin "18") (pinfunction "Y1_18") (pintype "tri_state"))
      (node (ref "IC21") (pin "15") (pinfunction "A_15") (pintype "input"))
      (node (ref "IC23") (pin "18") (pinfunction "Y1_18") (pintype "tri_state"))
      (node (ref "IC28") (pin "15") (pinfunction "A_15") (pintype "input"))
      (node (ref "IC30") (pin "18") (pinfunction "Y1_18") (pintype "tri_state"))
      (node (ref "IC36") (pin "14") (pinfunction "B5_14") (pintype "bidirectional"))
      (node (ref "IC37") (pin "14") (pinfunction "B5_14") (pintype "bidirectional"))
      (node (ref "IC6") (pin "15") (pinfunction "A_15") (pintype "input"))
      (node (ref "IC8") (pin "18") (pinfunction "Y1_18") (pintype "tri_state"))
      (node (ref "RN2") (pin "6") (pinfunction "1_6") (pintype "passive"))
    )
    (net (code "61") (name "ADATA13") (class "Default")
      (node (ref "IC14") (pin "1") (pinfunction "B_1") (pintype "input"))
      (node (ref "IC16") (pin "16") (pinfunction "Y2_16") (pintype "tri_state"))
      (node (ref "IC21") (pin "1") (pinfunction "B_1") (pintype "input"))
      (node (ref "IC23") (pin "16") (pinfunction "Y2_16") (pintype "tri_state"))
      (node (ref "IC28") (pin "1") (pinfunction "B_1") (pintype "input"))
      (node (ref "IC30") (pin "16") (pinfunction "Y2_16") (pintype "tri_state"))
      (node (ref "IC36") (pin "13") (pinfunction "B6_13") (pintype "bidirectional"))
      (node (ref "IC37") (pin "13") (pinfunction "B6_13") (pintype "bidirectional"))
      (node (ref "IC6") (pin "1") (pinfunction "B_1") (pintype "input"))
      (node (ref "IC8") (pin "16") (pinfunction "Y2_16") (pintype "tri_state"))
      (node (ref "RN2") (pin "7") (pinfunction "1_7") (pintype "passive"))
    )
    (net (code "62") (name "ADATA14") (class "Default")
      (node (ref "IC14") (pin "10") (pinfunction "C_10") (pintype "input"))
      (node (ref "IC16") (pin "14") (pinfunction "Y3_14") (pintype "tri_state"))
      (node (ref "IC21") (pin "10") (pinfunction "C_10") (pintype "input"))
      (node (ref "IC23") (pin "14") (pinfunction "Y3_14") (pintype "tri_state"))
      (node (ref "IC28") (pin "10") (pinfunction "C_10") (pintype "input"))
      (node (ref "IC30") (pin "14") (pinfunction "Y3_14") (pintype "tri_state"))
      (node (ref "IC36") (pin "12") (pinfunction "B7_12") (pintype "bidirectional"))
      (node (ref "IC37") (pin "12") (pinfunction "B7_12") (pintype "bidirectional"))
      (node (ref "IC6") (pin "10") (pinfunction "C_10") (pintype "input"))
      (node (ref "IC8") (pin "14") (pinfunction "Y3_14") (pintype "tri_state"))
      (node (ref "RN2") (pin "8") (pinfunction "1_8") (pintype "passive"))
    )
    (net (code "63") (name "ADATA15") (class "Default")
      (node (ref "IC14") (pin "9") (pinfunction "D_9") (pintype "input"))
      (node (ref "IC16") (pin "12") (pinfunction "Y4_12") (pintype "tri_state"))
      (node (ref "IC21") (pin "9") (pinfunction "D_9") (pintype "input"))
      (node (ref "IC23") (pin "12") (pinfunction "Y4_12") (pintype "tri_state"))
      (node (ref "IC28") (pin "9") (pinfunction "D_9") (pintype "input"))
      (node (ref "IC30") (pin "12") (pinfunction "Y4_12") (pintype "tri_state"))
      (node (ref "IC36") (pin "11") (pinfunction "B8_11") (pintype "bidirectional"))
      (node (ref "IC37") (pin "11") (pinfunction "B8_11") (pintype "bidirectional"))
      (node (ref "IC6") (pin "9") (pinfunction "D_9") (pintype "input"))
      (node (ref "IC8") (pin "12") (pinfunction "Y4_12") (pintype "tri_state"))
      (node (ref "RN2") (pin "9") (pinfunction "1_9") (pintype "passive"))
    )
    (net (code "64") (name "ADDR0") (class "Default")
      (node (ref "X1") (pin "A3") (pinfunction "B_A3") (pintype "passive"))
    )
    (net (code "65") (name "ADDR1") (class "Default")
      (node (ref "X1") (pin "A4") (pinfunction "B_A4") (pintype "passive"))
    )
    (net (code "66") (name "ADDR2") (class "Default")
      (node (ref "X1") (pin "A5") (pinfunction "B_A5") (pintype "passive"))
    )
    (net (code "67") (name "ADDR3") (class "Default")
      (node (ref "X1") (pin "A6") (pinfunction "B_A6") (pintype "passive"))
    )
    (net (code "68") (name "ADDR4") (class "Default")
      (node (ref "X1") (pin "A7") (pinfunction "B_A7") (pintype "passive"))
    )
    (net (code "69") (name "ADDR5") (class "Default")
      (node (ref "X1") (pin "A8") (pinfunction "B_A8") (pintype "passive"))
    )
    (net (code "70") (name "ADDR6") (class "Default")
      (node (ref "X1") (pin "A9") (pinfunction "B_A9") (pintype "passive"))
    )
    (net (code "71") (name "ADDR7") (class "Default")
      (node (ref "X1") (pin "A10") (pinfunction "B_A10") (pintype "passive"))
    )
    (net (code "72") (name "ADDR8") (class "Default")
      (node (ref "X1") (pin "A11") (pinfunction "B_A11") (pintype "passive"))
    )
    (net (code "73") (name "ADDR9") (class "Default")
      (node (ref "X1") (pin "A12") (pinfunction "B_A12") (pintype "passive"))
    )
    (net (code "74") (name "ADDR10") (class "Default")
      (node (ref "X1") (pin "A13") (pinfunction "B_A13") (pintype "passive"))
    )
    (net (code "75") (name "ADDR11") (class "Default")
      (node (ref "X1") (pin "A14") (pinfunction "B_A14") (pintype "passive"))
    )
    (net (code "76") (name "ADDR12") (class "Default")
      (node (ref "X1") (pin "A15") (pinfunction "B_A15") (pintype "passive"))
    )
    (net (code "77") (name "ADDR13") (class "Default")
      (node (ref "X1") (pin "A16") (pinfunction "B_A16") (pintype "passive"))
    )
    (net (code "78") (name "ADDR14") (class "Default")
      (node (ref "X1") (pin "A17") (pinfunction "B_A17") (pintype "passive"))
    )
    (net (code "79") (name "ADDR15") (class "Default")
      (node (ref "X1") (pin "A18") (pinfunction "B_A18") (pintype "passive"))
    )
    (net (code "80") (name "ALU0") (class "Default")
      (node (ref "X1") (pin "C16") (pinfunction "B_C16") (pintype "passive"))
    )
    (net (code "81") (name "ALU1") (class "Default")
      (node (ref "X1") (pin "C17") (pinfunction "B_C17") (pintype "passive"))
    )
    (net (code "82") (name "ALU2") (class "Default")
      (node (ref "X1") (pin "C18") (pinfunction "B_C18") (pintype "passive"))
    )
    (net (code "83") (name "ALU3") (class "Default")
      (node (ref "X1") (pin "C19") (pinfunction "B_C19") (pintype "passive"))
    )
    (net (code "84") (name "BR-COND") (class "Default")
      (node (ref "X1") (pin "C24") (pinfunction "B_C24") (pintype "passive"))
    )
    (net (code "85") (name "BUS-DIR") (class "Default")
      (node (ref "IC35") (pin "1") (pinfunction "DIR_1") (pintype "input"))
      (node (ref "IC36") (pin "1") (pinfunction "DIR_1") (pintype "input"))
      (node (ref "IC37") (pin "1") (pinfunction "DIR_1") (pintype "input"))
      (node (ref "IC38") (pin "3") (pinfunction "O_3") (pintype "open_collector"))
    )
    (net (code "86") (name "DATA0") (class "Default")
      (node (ref "IC35") (pin "2") (pinfunction "A1_2") (pintype "bidirectional"))
      (node (ref "IC37") (pin "2") (pinfunction "A1_2") (pintype "bidirectional"))
      (node (ref "X1") (pin "A19") (pinfunction "B_A19") (pintype "passive"))
    )
    (net (code "87") (name "DATA1") (class "Default")
      (node (ref "IC35") (pin "3") (pinfunction "A2_3") (pintype "bidirectional"))
      (node (ref "IC37") (pin "3") (pinfunction "A2_3") (pintype "bidirectional"))
      (node (ref "X1") (pin "A20") (pinfunction "B_A20") (pintype "passive"))
    )
    (net (code "88") (name "DATA2") (class "Default")
      (node (ref "IC35") (pin "4") (pinfunction "A3_4") (pintype "bidirectional"))
      (node (ref "IC37") (pin "4") (pinfunction "A3_4") (pintype "bidirectional"))
      (node (ref "X1") (pin "A21") (pinfunction "B_A21") (pintype "passive"))
    )
    (net (code "89") (name "DATA3") (class "Default")
      (node (ref "IC35") (pin "5") (pinfunction "A4_5") (pintype "bidirectional"))
      (node (ref "IC37") (pin "5") (pinfunction "A4_5") (pintype "bidirectional"))
      (node (ref "X1") (pin "A22") (pinfunction "B_A22") (pintype "passive"))
    )
    (net (code "90") (name "DATA4") (class "Default")
      (node (ref "IC35") (pin "6") (pinfunction "A5_6") (pintype "bidirectional"))
      (node (ref "IC37") (pin "6") (pinfunction "A5_6") (pintype "bidirectional"))
      (node (ref "X1") (pin "A23") (pinfunction "B_A23") (pintype "passive"))
    )
    (net (code "91") (name "DATA5") (class "Default")
      (node (ref "IC35") (pin "7") (pinfunction "A6_7") (pintype "bidirectional"))
      (node (ref "IC37") (pin "7") (pinfunction "A6_7") (pintype "bidirectional"))
      (node (ref "X1") (pin "A24") (pinfunction "B_A24") (pintype "passive"))
    )
    (net (code "92") (name "DATA6") (class "Default")
      (node (ref "IC35") (pin "8") (pinfunction "A7_8") (pintype "bidirectional"))
      (node (ref "IC37") (pin "8") (pinfunction "A7_8") (pintype "bidirectional"))
      (node (ref "X1") (pin "A25") (pinfunction "B_A25") (pintype "passive"))
    )
    (net (code "93") (name "DATA7") (class "Default")
      (node (ref "IC35") (pin "9") (pinfunction "A8_9") (pintype "bidirectional"))
      (node (ref "IC37") (pin "9") (pinfunction "A8_9") (pintype "bidirectional"))
      (node (ref "X1") (pin "A26") (pinfunction "B_A26") (pintype "passive"))
    )
    (net (code "94") (name "DATA8") (class "Default")
      (node (ref "IC36") (pin "2") (pinfunction "A1_2") (pintype "bidirectional"))
      (node (ref "X1") (pin "A27") (pinfunction "B_A27") (pintype "passive"))
    )
    (net (code "95") (name "DATA9") (class "Default")
      (node (ref "IC36") (pin "3") (pinfunction "A2_3") (pintype "bidirectional"))
      (node (ref "X1") (pin "A28") (pinfunction "B_A28") (pintype "passive"))
    )
    (net (code "96") (name "DATA10") (class "Default")
      (node (ref "IC36") (pin "4") (pinfunction "A3_4") (pintype "bidirectional"))
      (node (ref "X1") (pin "A29") (pinfunction "B_A29") (pintype "passive"))
    )
    (net (code "97") (name "DATA11") (class "Default")
      (node (ref "IC36") (pin "5") (pinfunction "A4_5") (pintype "bidirectional"))
      (node (ref "X1") (pin "A30") (pinfunction "B_A30") (pintype "passive"))
    )
    (net (code "98") (name "DATA12") (class "Default")
      (node (ref "IC36") (pin "6") (pinfunction "A5_6") (pintype "bidirectional"))
      (node (ref "X1") (pin "B3") (pinfunction "B_B3") (pintype "passive"))
    )
    (net (code "99") (name "DATA13") (class "Default")
      (node (ref "IC36") (pin "7") (pinfunction "A6_7") (pintype "bidirectional"))
      (node (ref "X1") (pin "B4") (pinfunction "B_B4") (pintype "passive"))
    )
    (net (code "100") (name "DATA14") (class "Default")
      (node (ref "IC36") (pin "8") (pinfunction "A7_8") (pintype "bidirectional"))
      (node (ref "X1") (pin "B5") (pinfunction "B_B5") (pintype "passive"))
    )
    (net (code "101") (name "DATA15") (class "Default")
      (node (ref "IC36") (pin "9") (pinfunction "A8_9") (pintype "bidirectional"))
      (node (ref "X1") (pin "B6") (pinfunction "B_B6") (pintype "passive"))
    )
    (net (code "102") (name "GND") (class "Default")
      (node (ref "C1") (pin "2") (pinfunction "2_2") (pintype "passive"))
      (node (ref "C10") (pin "2") (pinfunction "2_2") (pintype "passive"))
      (node (ref "C11") (pin "2") (pinfunction "2_2") (pintype "passive"))
      (node (ref "C12") (pin "2") (pinfunction "2_2") (pintype "passive"))
      (node (ref "C13") (pin "2") (pinfunction "2_2") (pintype "passive"))
      (node (ref "C14") (pin "2") (pinfunction "2_2") (pintype "passive"))
      (node (ref "C15") (pin "2") (pinfunction "2_2") (pintype "passive"))
      (node (ref "C16") (pin "2") (pinfunction "2_2") (pintype "passive"))
      (node (ref "C17") (pin "2") (pinfunction "2_2") (pintype "passive"))
      (node (ref "C18") (pin "2") (pinfunction "2_2") (pintype "passive"))
      (node (ref "C19") (pin "2") (pinfunction "2_2") (pintype "passive"))
      (node (ref "C2") (pin "2") (pinfunction "2_2") (pintype "passive"))
      (node (ref "C20") (pin "2") (pinfunction "2_2") (pintype "passive"))
      (node (ref "C21") (pin "2") (pinfunction "2_2") (pintype "passive"))
      (node (ref "C22") (pin "2") (pinfunction "2_2") (pintype "passive"))
      (node (ref "C23") (pin "2") (pinfunction "2_2") (pintype "passive"))
      (node (ref "C24") (pin "2") (pinfunction "2_2") (pintype "passive"))
      (node (ref "C25") (pin "2") (pinfunction "2_2") (pintype "passive"))
      (node (ref "C26") (pin "2") (pinfunction "2_2") (pintype "passive"))
      (node (ref "C27") (pin "2") (pinfunction "2_2") (pintype "passive"))
      (node (ref "C28") (pin "2") (pinfunction "2_2") (pintype "passive"))
      (node (ref "C29") (pin "2") (pinfunction "2_2") (pintype "passive"))
      (node (ref "C3") (pin "2") (pinfunction "2_2") (pintype "passive"))
      (node (ref "C30") (pin "2") (pinfunction "2_2") (pintype "passive"))
      (node (ref "C31") (pin "2") (pinfunction "2_2") (pintype "passive"))
      (node (ref "C32") (pin "2") (pinfunction "2_2") (pintype "passive"))
      (node (ref "C33") (pin "2") (pinfunction "2_2") (pintype "passive"))
      (node (ref "C34") (pin "2") (pinfunction "2_2") (pintype "passive"))
      (node (ref "C35") (pin "2") (pinfunction "2_2") (pintype "passive"))
      (node (ref "C36") (pin "2") (pinfunction "2_2") (pintype "passive"))
      (node (ref "C37") (pin "2") (pinfunction "2_2") (pintype "passive"))
      (node (ref "C38") (pin "2") (pinfunction "2_2") (pintype "passive"))
      (node (ref "C4") (pin "2") (pinfunction "2_2") (pintype "passive"))
      (node (ref "C5") (pin "2") (pinfunction "2_2") (pintype "passive"))
      (node (ref "C6") (pin "2") (pinfunction "2_2") (pintype "passive"))
      (node (ref "C8") (pin "2") (pinfunction "2_2") (pintype "passive"))
      (node (ref "C9") (pin "2") (pinfunction "2_2") (pintype "passive"))
      (node (ref "IC38") (pin "1") (pinfunction "I0_1") (pintype "input"))
      (node (ref "IC38") (pin "5") (pinfunction "I0_5") (pintype "input"))
      (node (ref "IC38") (pin "8") (pinfunction "I0_8") (pintype "input"))
      (node (ref "JP1") (pin "1") (pinfunction "1_1") (pintype "passive"))
      (node (ref "JP1") (pin "2") (pinfunction "2_2") (pintype "passive"))
      (node (ref "JP1") (pin "39") (pinfunction "39_39") (pintype "passive"))
      (node (ref "JP1") (pin "40") (pinfunction "40_40") (pintype "passive"))
      (node (ref "JP2") (pin "1") (pinfunction "1_1") (pintype "passive"))
      (node (ref "JP2") (pin "2") (pinfunction "2_2") (pintype "passive"))
      (node (ref "JP2") (pin "39") (pinfunction "39_39") (pintype "passive"))
      (node (ref "JP2") (pin "40") (pinfunction "40_40") (pintype "passive"))
      (node (ref "PWR") (pin "K") (pinfunction "C_K") (pintype "passive"))
      (node (ref "X1") (pin "A1") (pinfunction "B_A1") (pintype "passive"))
      (node (ref "X1") (pin "A32") (pinfunction "B_A32") (pintype "passive"))
      (node (ref "X1") (pin "B1") (pinfunction "B_B1") (pintype "passive"))
      (node (ref "X1") (pin "B32") (pinfunction "B_B32") (pintype "passive"))
      (node (ref "X1") (pin "C1") (pinfunction "B_C1") (pintype "passive"))
      (node (ref "X1") (pin "C32") (pinfunction "B_C32") (pintype "passive"))
    )
    (net (code "103") (name "IA-0") (class "Default")
      (node (ref "IC11") (pin "3") (pinfunction "QA_3") (pintype "output"))
      (node (ref "IC15") (pin "11") (pinfunction "A1_11") (pintype "input"))
      (node (ref "JP2") (pin "5") (pinfunction "5_5") (pintype "passive"))
    )
    (net (code "104") (name "IA-1") (class "Default")
      (node (ref "IC11") (pin "2") (pinfunction "QB_2") (pintype "output"))
      (node (ref "IC15") (pin "13") (pinfunction "A2_13") (pintype "input"))
      (node (ref "JP2") (pin "7") (pinfunction "7_7") (pintype "passive"))
    )
    (net (code "105") (name "IA-2") (class "Default")
      (node (ref "IC11") (pin "6") (pinfunction "QC_6") (pintype "output"))
      (node (ref "IC15") (pin "15") (pinfunction "A3_15") (pintype "input"))
      (node (ref "JP2") (pin "9") (pinfunction "9_9") (pintype "passive"))
    )
    (net (code "106") (name "IA-3") (class "Default")
      (node (ref "IC11") (pin "7") (pinfunction "QD_7") (pintype "output"))
      (node (ref "IC15") (pin "17") (pinfunction "A4_17") (pintype "input"))
      (node (ref "JP2") (pin "11") (pinfunction "11_11") (pintype "passive"))
    )
    (net (code "107") (name "IA-4") (class "Default")
      (node (ref "IC12") (pin "3") (pinfunction "QA_3") (pintype "output"))
      (node (ref "IC15") (pin "2") (pinfunction "A1_2") (pintype "input"))
      (node (ref "JP2") (pin "13") (pinfunction "13_13") (pintype "passive"))
    )
    (net (code "108") (name "IA-5") (class "Default")
      (node (ref "IC12") (pin "2") (pinfunction "QB_2") (pintype "output"))
      (node (ref "IC15") (pin "4") (pinfunction "A2_4") (pintype "input"))
      (node (ref "JP2") (pin "15") (pinfunction "15_15") (pintype "passive"))
    )
    (net (code "109") (name "IA-6") (class "Default")
      (node (ref "IC12") (pin "6") (pinfunction "QC_6") (pintype "output"))
      (node (ref "IC15") (pin "6") (pinfunction "A3_6") (pintype "input"))
      (node (ref "JP2") (pin "17") (pinfunction "17_17") (pintype "passive"))
    )
    (net (code "110") (name "IA-7") (class "Default")
      (node (ref "IC12") (pin "7") (pinfunction "QD_7") (pintype "output"))
      (node (ref "IC15") (pin "8") (pinfunction "A4_8") (pintype "input"))
      (node (ref "JP2") (pin "19") (pinfunction "19_19") (pintype "passive"))
    )
    (net (code "111") (name "IA-8") (class "Default")
      (node (ref "IC13") (pin "3") (pinfunction "QA_3") (pintype "output"))
      (node (ref "IC16") (pin "11") (pinfunction "A1_11") (pintype "input"))
      (node (ref "JP2") (pin "21") (pinfunction "21_21") (pintype "passive"))
    )
    (net (code "112") (name "IA-9") (class "Default")
      (node (ref "IC13") (pin "2") (pinfunction "QB_2") (pintype "output"))
      (node (ref "IC16") (pin "13") (pinfunction "A2_13") (pintype "input"))
      (node (ref "JP2") (pin "23") (pinfunction "23_23") (pintype "passive"))
    )
    (net (code "113") (name "IA-10") (class "Default")
      (node (ref "IC13") (pin "6") (pinfunction "QC_6") (pintype "output"))
      (node (ref "IC16") (pin "15") (pinfunction "A3_15") (pintype "input"))
      (node (ref "JP2") (pin "25") (pinfunction "25_25") (pintype "passive"))
    )
    (net (code "114") (name "IA-11") (class "Default")
      (node (ref "IC13") (pin "7") (pinfunction "QD_7") (pintype "output"))
      (node (ref "IC16") (pin "17") (pinfunction "A4_17") (pintype "input"))
      (node (ref "JP2") (pin "27") (pinfunction "27_27") (pintype "passive"))
    )
    (net (code "115") (name "IA-12") (class "Default")
      (node (ref "IC14") (pin "3") (pinfunction "QA_3") (pintype "output"))
      (node (ref "IC16") (pin "2") (pinfunction "A1_2") (pintype "input"))
      (node (ref "JP2") (pin "29") (pinfunction "29_29") (pintype "passive"))
    )
    (net (code "116") (name "IA-13") (class "Default")
      (node (ref "IC14") (pin "2") (pinfunction "QB_2") (pintype "output"))
      (node (ref "IC16") (pin "4") (pinfunction "A2_4") (pintype "input"))
      (node (ref "JP2") (pin "31") (pinfunction "31_31") (pintype "passive"))
    )
    (net (code "117") (name "IA-14") (class "Default")
      (node (ref "IC14") (pin "6") (pinfunction "QC_6") (pintype "output"))
      (node (ref "IC16") (pin "6") (pinfunction "A3_6") (pintype "input"))
      (node (ref "JP2") (pin "33") (pinfunction "33_33") (pintype "passive"))
    )
    (net (code "118") (name "IA-15") (class "Default")
      (node (ref "IC14") (pin "7") (pinfunction "QD_7") (pintype "output"))
      (node (ref "IC16") (pin "8") (pinfunction "A4_8") (pintype "input"))
      (node (ref "JP2") (pin "35") (pinfunction "35_35") (pintype "passive"))
    )
    (net (code "119") (name "IB-0") (class "Default")
      (node (ref "JP2") (pin "6") (pinfunction "6_6") (pintype "passive"))
    )
    (net (code "120") (name "IB-1") (class "Default")
      (node (ref "JP2") (pin "8") (pinfunction "8_8") (pintype "passive"))
    )
    (net (code "121") (name "IB-2") (class "Default")
      (node (ref "JP2") (pin "10") (pinfunction "10_10") (pintype "passive"))
    )
    (net (code "122") (name "IB-3") (class "Default")
      (node (ref "JP2") (pin "12") (pinfunction "12_12") (pintype "passive"))
    )
    (net (code "123") (name "IB-4") (class "Default")
      (node (ref "JP2") (pin "14") (pinfunction "14_14") (pintype "passive"))
    )
    (net (code "124") (name "IB-5") (class "Default")
      (node (ref "JP2") (pin "16") (pinfunction "16_16") (pintype "passive"))
    )
    (net (code "125") (name "IB-6") (class "Default")
      (node (ref "JP2") (pin "18") (pinfunction "18_18") (pintype "passive"))
    )
    (net (code "126") (name "IB-7") (class "Default")
      (node (ref "JP2") (pin "20") (pinfunction "20_20") (pintype "passive"))
    )
    (net (code "127") (name "IB-8") (class "Default")
      (node (ref "JP2") (pin "22") (pinfunction "22_22") (pintype "passive"))
    )
    (net (code "128") (name "IB-9") (class "Default")
      (node (ref "JP2") (pin "24") (pinfunction "24_24") (pintype "passive"))
    )
    (net (code "129") (name "IB-10") (class "Default")
      (node (ref "JP2") (pin "26") (pinfunction "26_26") (pintype "passive"))
    )
    (net (code "130") (name "IB-11") (class "Default")
      (node (ref "JP2") (pin "28") (pinfunction "28_28") (pintype "passive"))
    )
    (net (code "131") (name "IB-12") (class "Default")
      (node (ref "JP2") (pin "30") (pinfunction "30_30") (pintype "passive"))
    )
    (net (code "132") (name "IB-13") (class "Default")
      (node (ref "JP2") (pin "32") (pinfunction "32_32") (pintype "passive"))
    )
    (net (code "133") (name "IB-14") (class "Default")
      (node (ref "JP2") (pin "34") (pinfunction "34_34") (pintype "passive"))
    )
    (net (code "134") (name "IB-15") (class "Default")
      (node (ref "JP2") (pin "36") (pinfunction "36_36") (pintype "passive"))
    )
    (net (code "135") (name "IC-0") (class "Default")
      (node (ref "IC25") (pin "3") (pinfunction "QA_3") (pintype "output"))
      (node (ref "IC29") (pin "11") (pinfunction "A1_11") (pintype "input"))
      (node (ref "JP1") (pin "5") (pinfunction "5_5") (pintype "passive"))
    )
    (net (code "136") (name "IC-1") (class "Default")
      (node (ref "IC25") (pin "2") (pinfunction "QB_2") (pintype "output"))
      (node (ref "IC29") (pin "13") (pinfunction "A2_13") (pintype "input"))
      (node (ref "JP1") (pin "7") (pinfunction "7_7") (pintype "passive"))
    )
    (net (code "137") (name "IC-2") (class "Default")
      (node (ref "IC25") (pin "6") (pinfunction "QC_6") (pintype "output"))
      (node (ref "IC29") (pin "15") (pinfunction "A3_15") (pintype "input"))
      (node (ref "JP1") (pin "9") (pinfunction "9_9") (pintype "passive"))
    )
    (net (code "138") (name "IC-3") (class "Default")
      (node (ref "IC25") (pin "7") (pinfunction "QD_7") (pintype "output"))
      (node (ref "IC29") (pin "17") (pinfunction "A4_17") (pintype "input"))
      (node (ref "JP1") (pin "11") (pinfunction "11_11") (pintype "passive"))
    )
    (net (code "139") (name "IC-4") (class "Default")
      (node (ref "IC26") (pin "3") (pinfunction "QA_3") (pintype "output"))
      (node (ref "IC29") (pin "2") (pinfunction "A1_2") (pintype "input"))
      (node (ref "JP1") (pin "13") (pinfunction "13_13") (pintype "passive"))
    )
    (net (code "140") (name "IC-5") (class "Default")
      (node (ref "IC26") (pin "2") (pinfunction "QB_2") (pintype "output"))
      (node (ref "IC29") (pin "4") (pinfunction "A2_4") (pintype "input"))
      (node (ref "JP1") (pin "15") (pinfunction "15_15") (pintype "passive"))
    )
    (net (code "141") (name "IC-6") (class "Default")
      (node (ref "IC26") (pin "6") (pinfunction "QC_6") (pintype "output"))
      (node (ref "IC29") (pin "6") (pinfunction "A3_6") (pintype "input"))
      (node (ref "JP1") (pin "17") (pinfunction "17_17") (pintype "passive"))
    )
    (net (code "142") (name "IC-7") (class "Default")
      (node (ref "IC26") (pin "7") (pinfunction "QD_7") (pintype "output"))
      (node (ref "IC29") (pin "8") (pinfunction "A4_8") (pintype "input"))
      (node (ref "JP1") (pin "19") (pinfunction "19_19") (pintype "passive"))
    )
    (net (code "143") (name "IC-8") (class "Default")
      (node (ref "IC27") (pin "3") (pinfunction "QA_3") (pintype "output"))
      (node (ref "IC30") (pin "11") (pinfunction "A1_11") (pintype "input"))
      (node (ref "JP1") (pin "21") (pinfunction "21_21") (pintype "passive"))
    )
    (net (code "144") (name "IC-9") (class "Default")
      (node (ref "IC27") (pin "2") (pinfunction "QB_2") (pintype "output"))
      (node (ref "IC30") (pin "13") (pinfunction "A2_13") (pintype "input"))
      (node (ref "JP1") (pin "23") (pinfunction "23_23") (pintype "passive"))
    )
    (net (code "145") (name "IC-10") (class "Default")
      (node (ref "IC27") (pin "6") (pinfunction "QC_6") (pintype "output"))
      (node (ref "IC30") (pin "15") (pinfunction "A3_15") (pintype "input"))
      (node (ref "JP1") (pin "25") (pinfunction "25_25") (pintype "passive"))
    )
    (net (code "146") (name "IC-11") (class "Default")
      (node (ref "IC27") (pin "7") (pinfunction "QD_7") (pintype "output"))
      (node (ref "IC30") (pin "17") (pinfunction "A4_17") (pintype "input"))
      (node (ref "JP1") (pin "27") (pinfunction "27_27") (pintype "passive"))
    )
    (net (code "147") (name "IC-12") (class "Default")
      (node (ref "IC28") (pin "3") (pinfunction "QA_3") (pintype "output"))
      (node (ref "IC30") (pin "2") (pinfunction "A1_2") (pintype "input"))
    )
    (net (code "148") (name "IC-13") (class "Default")
      (node (ref "IC28") (pin "2") (pinfunction "QB_2") (pintype "output"))
      (node (ref "IC30") (pin "4") (pinfunction "A2_4") (pintype "input"))
      (node (ref "JP1") (pin "31") (pinfunction "31_31") (pintype "passive"))
    )
    (net (code "149") (name "IC-14") (class "Default")
      (node (ref "IC28") (pin "6") (pinfunction "QC_6") (pintype "output"))
      (node (ref "IC30") (pin "6") (pinfunction "A3_6") (pintype "input"))
      (node (ref "JP1") (pin "33") (pinfunction "33_33") (pintype "passive"))
    )
    (net (code "150") (name "IC-15") (class "Default")
      (node (ref "IC28") (pin "7") (pinfunction "QD_7") (pintype "output"))
      (node (ref "IC30") (pin "8") (pinfunction "A4_8") (pintype "input"))
      (node (ref "JP1") (pin "35") (pinfunction "35_35") (pintype "passive"))
    )
    (net (code "151") (name "ID-0") (class "Default")
      (node (ref "JP1") (pin "6") (pinfunction "6_6") (pintype "passive"))
    )
    (net (code "152") (name "ID-1") (class "Default")
      (node (ref "JP1") (pin "8") (pinfunction "8_8") (pintype "passive"))
    )
    (net (code "153") (name "ID-2") (class "Default")
      (node (ref "JP1") (pin "10") (pinfunction "10_10") (pintype "passive"))
    )
    (net (code "154") (name "ID-3") (class "Default")
      (node (ref "JP1") (pin "12") (pinfunction "12_12") (pintype "passive"))
    )
    (net (code "155") (name "ID-4") (class "Default")
      (node (ref "JP1") (pin "14") (pinfunction "14_14") (pintype "passive"))
    )
    (net (code "156") (name "ID-5") (class "Default")
      (node (ref "JP1") (pin "16") (pinfunction "16_16") (pintype "passive"))
    )
    (net (code "157") (name "ID-6") (class "Default")
      (node (ref "JP1") (pin "18") (pinfunction "18_18") (pintype "passive"))
    )
    (net (code "158") (name "ID-7") (class "Default")
      (node (ref "JP1") (pin "20") (pinfunction "20_20") (pintype "passive"))
    )
    (net (code "159") (name "ID-8") (class "Default")
      (node (ref "JP1") (pin "22") (pinfunction "22_22") (pintype "passive"))
    )
    (net (code "160") (name "ID-9") (class "Default")
      (node (ref "JP1") (pin "24") (pinfunction "24_24") (pintype "passive"))
    )
    (net (code "161") (name "ID-10") (class "Default")
      (node (ref "JP1") (pin "26") (pinfunction "26_26") (pintype "passive"))
    )
    (net (code "162") (name "ID-11") (class "Default")
      (node (ref "JP1") (pin "28") (pinfunction "28_28") (pintype "passive"))
    )
    (net (code "163") (name "ID-12") (class "Default")
      (node (ref "JP1") (pin "30") (pinfunction "30_30") (pintype "passive"))
    )
    (net (code "164") (name "ID-13") (class "Default")
      (node (ref "JP1") (pin "32") (pinfunction "32_32") (pintype "passive"))
    )
    (net (code "165") (name "ID-14") (class "Default")
      (node (ref "JP1") (pin "34") (pinfunction "34_34") (pintype "passive"))
    )
    (net (code "166") (name "ID-15") (class "Default")
      (node (ref "JP1") (pin "36") (pinfunction "36_36") (pintype "passive"))
    )
    (net (code "167") (name "IO-ADDR0") (class "Default")
      (node (ref "X1") (pin "C7") (pinfunction "B_C7") (pintype "passive"))
    )
    (net (code "168") (name "IO-ADDR1") (class "Default")
      (node (ref "X1") (pin "C8") (pinfunction "B_C8") (pintype "passive"))
    )
    (net (code "169") (name "IO-ADDR2") (class "Default")
      (node (ref "X1") (pin "C9") (pinfunction "B_C9") (pintype "passive"))
    )
    (net (code "170") (name "IO-ADDR3") (class "Default")
      (node (ref "X1") (pin "C10") (pinfunction "B_C10") (pintype "passive"))
    )
    (net (code "171") (name "Net-(IC1A-O)") (class "Default")
      (node (ref "IC1") (pin "3") (pinfunction "O_3") (pintype "output"))
      (node (ref "IC3") (pin "5") (pinfunction "UP_5") (pintype "input"))
    )
    (net (code "172") (name "Net-(IC1B-O)") (class "Default")
      (node (ref "IC1") (pin "6") (pinfunction "O_6") (pintype "output"))
      (node (ref "IC3") (pin "4") (pinfunction "DN_4") (pintype "input"))
    )
    (net (code "173") (name "Net-(IC1C-O)") (class "Default")
      (node (ref "IC1") (pin "8") (pinfunction "O_8") (pintype "output"))
      (node (ref "IC3") (pin "11") (pinfunction "LD_11") (pintype "input"))
      (node (ref "IC4") (pin "11") (pinfunction "LD_11") (pintype "input"))
    )
    (net (code "174") (name "Net-(IC1D-O)") (class "Default")
      (node (ref "IC1") (pin "11") (pinfunction "O_11") (pintype "output"))
      (node (ref "IC5") (pin "11") (pinfunction "LD_11") (pintype "input"))
      (node (ref "IC6") (pin "11") (pinfunction "LD_11") (pintype "input"))
    )
    (net (code "175") (name "Net-(IC2A-O)") (class "Default")
      (node (ref "IC2") (pin "3") (pinfunction "O_3") (pintype "output"))
      (node (ref "IC7") (pin "1") (pinfunction "G_1") (pintype "input"))
      (node (ref "IC7") (pin "19") (pinfunction "G_19") (pintype "input"))
    )
    (net (code "176") (name "Net-(IC2B-O)") (class "Default")
      (node (ref "IC2") (pin "6") (pinfunction "O_6") (pintype "output"))
      (node (ref "IC8") (pin "1") (pinfunction "G_1") (pintype "input"))
      (node (ref "IC8") (pin "19") (pinfunction "G_19") (pintype "input"))
    )
    (net (code "177") (name "Net-(IC3A-BO)") (class "Default")
      (node (ref "IC3") (pin "13") (pinfunction "BO_13") (pintype "output"))
      (node (ref "IC4") (pin "4") (pinfunction "DN_4") (pintype "input"))
    )
    (net (code "178") (name "Net-(IC3A-CO)") (class "Default")
      (node (ref "IC3") (pin "12") (pinfunction "CO_12") (pintype "output"))
      (node (ref "IC4") (pin "5") (pinfunction "UP_5") (pintype "input"))
    )
    (net (code "179") (name "Net-(IC3A-QA)") (class "Default")
      (node (ref "IC3") (pin "3") (pinfunction "QA_3") (pintype "output"))
      (node (ref "IC7") (pin "11") (pinfunction "A1_11") (pintype "input"))
    )
    (net (code "180") (name "Net-(IC3A-QB)") (class "Default")
      (node (ref "IC3") (pin "2") (pinfunction "QB_2") (pintype "output"))
      (node (ref "IC7") (pin "13") (pinfunction "A2_13") (pintype "input"))
    )
    (net (code "181") (name "Net-(IC3A-QC)") (class "Default")
      (node (ref "IC3") (pin "6") (pinfunction "QC_6") (pintype "output"))
      (node (ref "IC7") (pin "15") (pinfunction "A3_15") (pintype "input"))
    )
    (net (code "182") (name "Net-(IC3A-QD)") (class "Default")
      (node (ref "IC3") (pin "7") (pinfunction "QD_7") (pintype "output"))
      (node (ref "IC7") (pin "17") (pinfunction "A4_17") (pintype "input"))
    )
    (net (code "183") (name "Net-(IC4A-BO)") (class "Default")
      (node (ref "IC4") (pin "13") (pinfunction "BO_13") (pintype "output"))
      (node (ref "IC5") (pin "4") (pinfunction "DN_4") (pintype "input"))
    )
    (net (code "184") (name "Net-(IC4A-CO)") (class "Default")
      (node (ref "IC4") (pin "12") (pinfunction "CO_12") (pintype "output"))
      (node (ref "IC5") (pin "5") (pinfunction "UP_5") (pintype "input"))
    )
    (net (code "185") (name "Net-(IC4A-QA)") (class "Default")
      (node (ref "IC4") (pin "3") (pinfunction "QA_3") (pintype "output"))
      (node (ref "IC7") (pin "2") (pinfunction "A1_2") (pintype "input"))
    )
    (net (code "186") (name "Net-(IC4A-QB)") (class "Default")
      (node (ref "IC4") (pin "2") (pinfunction "QB_2") (pintype "output"))
      (node (ref "IC7") (pin "4") (pinfunction "A2_4") (pintype "input"))
    )
    (net (code "187") (name "Net-(IC4A-QC)") (class "Default")
      (node (ref "IC4") (pin "6") (pinfunction "QC_6") (pintype "output"))
      (node (ref "IC7") (pin "6") (pinfunction "A3_6") (pintype "input"))
    )
    (net (code "188") (name "Net-(IC4A-QD)") (class "Default")
      (node (ref "IC4") (pin "7") (pinfunction "QD_7") (pintype "output"))
      (node (ref "IC7") (pin "8") (pinfunction "A4_8") (pintype "input"))
    )
    (net (code "189") (name "Net-(IC5A-BO)") (class "Default")
      (node (ref "IC5") (pin "13") (pinfunction "BO_13") (pintype "output"))
      (node (ref "IC6") (pin "4") (pinfunction "DN_4") (pintype "input"))
    )
    (net (code "190") (name "Net-(IC5A-CO)") (class "Default")
      (node (ref "IC5") (pin "12") (pinfunction "CO_12") (pintype "output"))
      (node (ref "IC6") (pin "5") (pinfunction "UP_5") (pintype "input"))
    )
    (net (code "191") (name "Net-(IC5A-QA)") (class "Default")
      (node (ref "IC5") (pin "3") (pinfunction "QA_3") (pintype "output"))
      (node (ref "IC8") (pin "11") (pinfunction "A1_11") (pintype "input"))
    )
    (net (code "192") (name "Net-(IC5A-QB)") (class "Default")
      (node (ref "IC5") (pin "2") (pinfunction "QB_2") (pintype "output"))
      (node (ref "IC8") (pin "13") (pinfunction "A2_13") (pintype "input"))
    )
    (net (code "193") (name "Net-(IC5A-QC)") (class "Default")
      (node (ref "IC5") (pin "6") (pinfunction "QC_6") (pintype "output"))
      (node (ref "IC8") (pin "15") (pinfunction "A3_15") (pintype "input"))
    )
    (net (code "194") (name "Net-(IC5A-QD)") (class "Default")
      (node (ref "IC5") (pin "7") (pinfunction "QD_7") (pintype "output"))
      (node (ref "IC8") (pin "17") (pinfunction "A4_17") (pintype "input"))
    )
    (net (code "195") (name "Net-(IC6A-QA)") (class "Default")
      (node (ref "IC6") (pin "3") (pinfunction "QA_3") (pintype "output"))
      (node (ref "IC8") (pin "2") (pinfunction "A1_2") (pintype "input"))
    )
    (net (code "196") (name "Net-(IC6A-QB)") (class "Default")
      (node (ref "IC6") (pin "2") (pinfunction "QB_2") (pintype "output"))
      (node (ref "IC8") (pin "4") (pinfunction "A2_4") (pintype "input"))
    )
    (net (code "197") (name "Net-(IC6A-QC)") (class "Default")
      (node (ref "IC6") (pin "6") (pinfunction "QC_6") (pintype "output"))
      (node (ref "IC8") (pin "6") (pinfunction "A3_6") (pintype "input"))
    )
    (net (code "198") (name "Net-(IC6A-QD)") (class "Default")
      (node (ref "IC6") (pin "7") (pinfunction "QD_7") (pintype "output"))
      (node (ref "IC8") (pin "8") (pinfunction "A4_8") (pintype "input"))
    )
    (net (code "199") (name "Net-(IC10A-O)") (class "Default")
      (node (ref "IC10") (pin "3") (pinfunction "O_3") (pintype "output"))
      (node (ref "IC15") (pin "1") (pinfunction "G_1") (pintype "input"))
      (node (ref "IC15") (pin "19") (pinfunction "G_19") (pintype "input"))
    )
    (net (code "200") (name "Net-(IC10B-O)") (class "Default")
      (node (ref "IC10") (pin "6") (pinfunction "O_6") (pintype "output"))
      (node (ref "IC16") (pin "1") (pinfunction "G_1") (pintype "input"))
      (node (ref "IC16") (pin "19") (pinfunction "G_19") (pintype "input"))
    )
    (net (code "201") (name "Net-(IC10C-O)") (class "Default")
      (node (ref "IC10") (pin "8") (pinfunction "O_8") (pintype "output"))
      (node (ref "IC29") (pin "1") (pinfunction "G_1") (pintype "input"))
      (node (ref "IC29") (pin "19") (pinfunction "G_19") (pintype "input"))
    )
    (net (code "202") (name "Net-(IC10D-O)") (class "Default")
      (node (ref "IC10") (pin "11") (pinfunction "O_11") (pintype "output"))
      (node (ref "IC30") (pin "1") (pinfunction "G_1") (pintype "input"))
      (node (ref "IC30") (pin "19") (pinfunction "G_19") (pintype "input"))
    )
    (net (code "203") (name "Net-(IC11A-BO)") (class "Default")
      (node (ref "IC11") (pin "13") (pinfunction "BO_13") (pintype "output"))
      (node (ref "IC12") (pin "4") (pinfunction "DN_4") (pintype "input"))
    )
    (net (code "204") (name "Net-(IC11A-CO)") (class "Default")
      (node (ref "IC11") (pin "12") (pinfunction "CO_12") (pintype "output"))
      (node (ref "IC12") (pin "5") (pinfunction "UP_5") (pintype "input"))
    )
    (net (code "205") (name "Net-(IC11A-DN)") (class "Default")
      (node (ref "IC11") (pin "4") (pinfunction "DN_4") (pintype "input"))
      (node (ref "IC9") (pin "6") (pinfunction "O_6") (pintype "output"))
    )
    (net (code "206") (name "Net-(IC11A-LD)") (class "Default")
      (node (ref "IC11") (pin "11") (pinfunction "LD_11") (pintype "input"))
      (node (ref "IC12") (pin "11") (pinfunction "LD_11") (pintype "input"))
      (node (ref "IC9") (pin "8") (pinfunction "O_8") (pintype "output"))
    )
    (net (code "207") (name "Net-(IC11A-UP)") (class "Default")
      (node (ref "IC11") (pin "5") (pinfunction "UP_5") (pintype "input"))
      (node (ref "IC9") (pin "3") (pinfunction "O_3") (pintype "output"))
    )
    (net (code "208") (name "Net-(IC12A-BO)") (class "Default")
      (node (ref "IC12") (pin "13") (pinfunction "BO_13") (pintype "output"))
      (node (ref "IC13") (pin "4") (pinfunction "DN_4") (pintype "input"))
    )
    (net (code "209") (name "Net-(IC12A-CO)") (class "Default")
      (node (ref "IC12") (pin "12") (pinfunction "CO_12") (pintype "output"))
      (node (ref "IC13") (pin "5") (pinfunction "UP_5") (pintype "input"))
    )
    (net (code "210") (name "Net-(IC13A-BO)") (class "Default")
      (node (ref "IC13") (pin "13") (pinfunction "BO_13") (pintype "output"))
      (node (ref "IC14") (pin "4") (pinfunction "DN_4") (pintype "input"))
    )
    (net (code "211") (name "Net-(IC13A-CO)") (class "Default")
      (node (ref "IC13") (pin "12") (pinfunction "CO_12") (pintype "output"))
      (node (ref "IC14") (pin "5") (pinfunction "UP_5") (pintype "input"))
    )
    (net (code "212") (name "Net-(IC13A-LD)") (class "Default")
      (node (ref "IC13") (pin "11") (pinfunction "LD_11") (pintype "input"))
      (node (ref "IC14") (pin "11") (pinfunction "LD_11") (pintype "input"))
      (node (ref "IC9") (pin "11") (pinfunction "O_11") (pintype "output"))
    )
    (net (code "213") (name "Net-(IC17A-O)") (class "Default")
      (node (ref "IC17") (pin "3") (pinfunction "O_3") (pintype "output"))
      (node (ref "IC18") (pin "5") (pinfunction "UP_5") (pintype "input"))
    )
    (net (code "214") (name "Net-(IC17B-O)") (class "Default")
      (node (ref "IC17") (pin "6") (pinfunction "O_6") (pintype "output"))
      (node (ref "IC18") (pin "4") (pinfunction "DN_4") (pintype "input"))
    )
    (net (code "215") (name "Net-(IC17C-O)") (class "Default")
      (node (ref "IC17") (pin "8") (pinfunction "O_8") (pintype "output"))
      (node (ref "IC18") (pin "11") (pinfunction "LD_11") (pintype "input"))
      (node (ref "IC19") (pin "11") (pinfunction "LD_11") (pintype "input"))
    )
    (net (code "216") (name "Net-(IC17D-O)") (class "Default")
      (node (ref "IC17") (pin "11") (pinfunction "O_11") (pintype "output"))
      (node (ref "IC20") (pin "11") (pinfunction "LD_11") (pintype "input"))
      (node (ref "IC21") (pin "11") (pinfunction "LD_11") (pintype "input"))
    )
    (net (code "217") (name "Net-(IC18A-BO)") (class "Default")
      (node (ref "IC18") (pin "13") (pinfunction "BO_13") (pintype "output"))
      (node (ref "IC19") (pin "4") (pinfunction "DN_4") (pintype "input"))
    )
    (net (code "218") (name "Net-(IC18A-CO)") (class "Default")
      (node (ref "IC18") (pin "12") (pinfunction "CO_12") (pintype "output"))
      (node (ref "IC19") (pin "5") (pinfunction "UP_5") (pintype "input"))
    )
    (net (code "219") (name "Net-(IC18A-QA)") (class "Default")
      (node (ref "IC18") (pin "3") (pinfunction "QA_3") (pintype "output"))
      (node (ref "IC22") (pin "11") (pinfunction "A1_11") (pintype "input"))
    )
    (net (code "220") (name "Net-(IC18A-QB)") (class "Default")
      (node (ref "IC18") (pin "2") (pinfunction "QB_2") (pintype "output"))
      (node (ref "IC22") (pin "13") (pinfunction "A2_13") (pintype "input"))
    )
    (net (code "221") (name "Net-(IC18A-QC)") (class "Default")
      (node (ref "IC18") (pin "6") (pinfunction "QC_6") (pintype "output"))
      (node (ref "IC22") (pin "15") (pinfunction "A3_15") (pintype "input"))
    )
    (net (code "222") (name "Net-(IC18A-QD)") (class "Default")
      (node (ref "IC18") (pin "7") (pinfunction "QD_7") (pintype "output"))
      (node (ref "IC22") (pin "17") (pinfunction "A4_17") (pintype "input"))
    )
    (net (code "223") (name "Net-(IC19A-BO)") (class "Default")
      (node (ref "IC19") (pin "13") (pinfunction "BO_13") (pintype "output"))
      (node (ref "IC20") (pin "4") (pinfunction "DN_4") (pintype "input"))
    )
    (net (code "224") (name "Net-(IC19A-CO)") (class "Default")
      (node (ref "IC19") (pin "12") (pinfunction "CO_12") (pintype "output"))
      (node (ref "IC20") (pin "5") (pinfunction "UP_5") (pintype "input"))
    )
    (net (code "225") (name "Net-(IC19A-QA)") (class "Default")
      (node (ref "IC19") (pin "3") (pinfunction "QA_3") (pintype "output"))
      (node (ref "IC22") (pin "2") (pinfunction "A1_2") (pintype "input"))
    )
    (net (code "226") (name "Net-(IC19A-QB)") (class "Default")
      (node (ref "IC19") (pin "2") (pinfunction "QB_2") (pintype "output"))
      (node (ref "IC22") (pin "4") (pinfunction "A2_4") (pintype "input"))
    )
    (net (code "227") (name "Net-(IC19A-QC)") (class "Default")
      (node (ref "IC19") (pin "6") (pinfunction "QC_6") (pintype "output"))
      (node (ref "IC22") (pin "6") (pinfunction "A3_6") (pintype "input"))
    )
    (net (code "228") (name "Net-(IC19A-QD)") (class "Default")
      (node (ref "IC19") (pin "7") (pinfunction "QD_7") (pintype "output"))
      (node (ref "IC22") (pin "8") (pinfunction "A4_8") (pintype "input"))
    )
    (net (code "229") (name "Net-(IC20A-BO)") (class "Default")
      (node (ref "IC20") (pin "13") (pinfunction "BO_13") (pintype "output"))
      (node (ref "IC21") (pin "4") (pinfunction "DN_4") (pintype "input"))
    )
    (net (code "230") (name "Net-(IC20A-CO)") (class "Default")
      (node (ref "IC20") (pin "12") (pinfunction "CO_12") (pintype "output"))
      (node (ref "IC21") (pin "5") (pinfunction "UP_5") (pintype "input"))
    )
    (net (code "231") (name "Net-(IC20A-QA)") (class "Default")
      (node (ref "IC20") (pin "3") (pinfunction "QA_3") (pintype "output"))
      (node (ref "IC23") (pin "11") (pinfunction "A1_11") (pintype "input"))
    )
    (net (code "232") (name "Net-(IC20A-QB)") (class "Default")
      (node (ref "IC20") (pin "2") (pinfunction "QB_2") (pintype "output"))
      (node (ref "IC23") (pin "13") (pinfunction "A2_13") (pintype "input"))
    )
    (net (code "233") (name "Net-(IC20A-QC)") (class "Default")
      (node (ref "IC20") (pin "6") (pinfunction "QC_6") (pintype "output"))
      (node (ref "IC23") (pin "15") (pinfunction "A3_15") (pintype "input"))
    )
    (net (code "234") (name "Net-(IC20A-QD)") (class "Default")
      (node (ref "IC20") (pin "7") (pinfunction "QD_7") (pintype "output"))
      (node (ref "IC23") (pin "17") (pinfunction "A4_17") (pintype "input"))
    )
    (net (code "235") (name "Net-(IC21A-QA)") (class "Default")
      (node (ref "IC21") (pin "3") (pinfunction "QA_3") (pintype "output"))
      (node (ref "IC23") (pin "2") (pinfunction "A1_2") (pintype "input"))
    )
    (net (code "236") (name "Net-(IC21A-QB)") (class "Default")
      (node (ref "IC21") (pin "2") (pinfunction "QB_2") (pintype "output"))
      (node (ref "IC23") (pin "4") (pinfunction "A2_4") (pintype "input"))
    )
    (net (code "237") (name "Net-(IC21A-QC)") (class "Default")
      (node (ref "IC21") (pin "6") (pinfunction "QC_6") (pintype "output"))
      (node (ref "IC23") (pin "6") (pinfunction "A3_6") (pintype "input"))
    )
    (net (code "238") (name "Net-(IC21A-QD)") (class "Default")
      (node (ref "IC21") (pin "7") (pinfunction "QD_7") (pintype "output"))
      (node (ref "IC23") (pin "8") (pinfunction "A4_8") (pintype "input"))
    )
    (net (code "239") (name "Net-(IC22A-G)") (class "Default")
      (node (ref "IC2") (pin "8") (pinfunction "O_8") (pintype "output"))
      (node (ref "IC22") (pin "1") (pinfunction "G_1") (pintype "input"))
      (node (ref "IC22") (pin "19") (pinfunction "G_19") (pintype "input"))
    )
    (net (code "240") (name "Net-(IC23A-G)") (class "Default")
      (node (ref "IC2") (pin "11") (pinfunction "O_11") (pintype "output"))
      (node (ref "IC23") (pin "1") (pinfunction "G_1") (pintype "input"))
      (node (ref "IC23") (pin "19") (pinfunction "G_19") (pintype "input"))
    )
    (net (code "241") (name "Net-(IC24A-O)") (class "Default")
      (node (ref "IC24") (pin "3") (pinfunction "O_3") (pintype "output"))
      (node (ref "IC25") (pin "5") (pinfunction "UP_5") (pintype "input"))
    )
    (net (code "242") (name "Net-(IC24B-O)") (class "Default")
      (node (ref "IC24") (pin "6") (pinfunction "O_6") (pintype "output"))
      (node (ref "IC25") (pin "4") (pinfunction "DN_4") (pintype "input"))
    )
    (net (code "243") (name "Net-(IC24C-O)") (class "Default")
      (node (ref "IC24") (pin "8") (pinfunction "O_8") (pintype "output"))
      (node (ref "IC25") (pin "11") (pinfunction "LD_11") (pintype "input"))
      (node (ref "IC26") (pin "11") (pinfunction "LD_11") (pintype "input"))
    )
    (net (code "244") (name "Net-(IC24D-O)") (class "Default")
      (node (ref "IC24") (pin "11") (pinfunction "O_11") (pintype "output"))
      (node (ref "IC27") (pin "11") (pinfunction "LD_11") (pintype "input"))
      (node (ref "IC28") (pin "11") (pinfunction "LD_11") (pintype "input"))
    )
    (net (code "245") (name "Net-(IC25A-BO)") (class "Default")
      (node (ref "IC25") (pin "13") (pinfunction "BO_13") (pintype "output"))
      (node (ref "IC26") (pin "4") (pinfunction "DN_4") (pintype "input"))
    )
    (net (code "246") (name "Net-(IC25A-CO)") (class "Default")
      (node (ref "IC25") (pin "12") (pinfunction "CO_12") (pintype "output"))
      (node (ref "IC26") (pin "5") (pinfunction "UP_5") (pintype "input"))
    )
    (net (code "247") (name "Net-(IC26A-BO)") (class "Default")
      (node (ref "IC26") (pin "13") (pinfunction "BO_13") (pintype "output"))
      (node (ref "IC27") (pin "4") (pinfunction "DN_4") (pintype "input"))
    )
    (net (code "248") (name "Net-(IC26A-CO)") (class "Default")
      (node (ref "IC26") (pin "12") (pinfunction "CO_12") (pintype "output"))
      (node (ref "IC27") (pin "5") (pinfunction "UP_5") (pintype "input"))
    )
    (net (code "249") (name "Net-(IC27A-BO)") (class "Default")
      (node (ref "IC27") (pin "13") (pinfunction "BO_13") (pintype "output"))
      (node (ref "IC28") (pin "4") (pinfunction "DN_4") (pintype "input"))
    )
    (net (code "250") (name "Net-(IC27A-CO)") (class "Default")
      (node (ref "IC27") (pin "12") (pinfunction "CO_12") (pintype "output"))
      (node (ref "IC28") (pin "5") (pinfunction "UP_5") (pintype "input"))
    )
    (net (code "251") (name "Net-(IC31A-O)") (class "Default")
      (node (ref "IC31") (pin "3") (pinfunction "O_3") (pintype "output"))
      (node (ref "IC32") (pin "1") (pinfunction "G_1") (pintype "input"))
    )
    (net (code "252") (name "Net-(IC31B-O)") (class "Default")
      (node (ref "IC31") (pin "6") (pinfunction "O_6") (pintype "output"))
      (node (ref "IC32") (pin "15") (pinfunction "G_15") (pintype "input"))
    )
    (net (code "253") (name "Net-(IC31C-I0)") (class "Default")
      (node (ref "IC31") (pin "9") (pinfunction "I0_9") (pintype "input"))
      (node (ref "IC38") (pin "4") (pinfunction "O_4") (pintype "open_collector"))
    )
    (net (code "254") (name "Net-(IC31C-I1)") (class "Default")
      (node (ref "IC31") (pin "10") (pinfunction "I1_10") (pintype "input"))
      (node (ref "IC31") (pin "12") (pinfunction "I0_12") (pintype "input"))
      (node (ref "IC38") (pin "11") (pinfunction "O_11") (pintype "open_collector"))
    )
    (net (code "255") (name "Net-(IC31C-O)") (class "Default")
      (node (ref "IC31") (pin "8") (pinfunction "O_8") (pintype "output"))
      (node (ref "IC35") (pin "19") (pinfunction "G_19") (pintype "input"))
      (node (ref "IC36") (pin "19") (pinfunction "G_19") (pintype "input"))
    )
    (net (code "256") (name "Net-(IC31D-O)") (class "Default")
      (node (ref "IC31") (pin "11") (pinfunction "O_11") (pintype "output"))
      (node (ref "IC37") (pin "19") (pinfunction "G_19") (pintype "input"))
    )
    (net (code "257") (name "Net-(IC32A-Y1)") (class "Default")
      (node (ref "IC32") (pin "5") (pinfunction "Y1_5") (pintype "output"))
      (node (ref "J1") (pin "3") (pinfunction "3_3") (pintype "passive"))
    )
    (net (code "258") (name "Net-(IC32A-Y2)") (class "Default")
      (node (ref "IC32") (pin "6") (pinfunction "Y2_6") (pintype "output"))
      (node (ref "J1") (pin "5") (pinfunction "5_5") (pintype "passive"))
    )
    (net (code "259") (name "Net-(IC32A-Y3)") (class "Default")
      (node (ref "IC32") (pin "7") (pinfunction "Y3_7") (pintype "output"))
      (node (ref "J1") (pin "7") (pinfunction "7_7") (pintype "passive"))
    )
    (net (code "260") (name "Net-(IC32B-Y1)") (class "Default")
      (node (ref "IC32") (pin "11") (pinfunction "Y1_11") (pintype "output"))
      (node (ref "J2") (pin "3") (pinfunction "3_3") (pintype "passive"))
    )
    (net (code "261") (name "Net-(IC32B-Y2)") (class "Default")
      (node (ref "IC32") (pin "10") (pinfunction "Y2_10") (pintype "output"))
      (node (ref "J2") (pin "5") (pinfunction "5_5") (pintype "passive"))
    )
    (net (code "262") (name "Net-(IC32B-Y3)") (class "Default")
      (node (ref "IC32") (pin "9") (pinfunction "Y3_9") (pintype "output"))
      (node (ref "J2") (pin "7") (pinfunction "7_7") (pintype "passive"))
    )
    (net (code "263") (name "Net-(PWR-PadA)") (class "Default")
      (node (ref "PWR") (pin "A") (pinfunction "A_A") (pintype "passive"))
      (node (ref "R1") (pin "1") (pinfunction "1_1") (pintype "passive"))
    )
    (net (code "264") (name "REG-LD-ID0") (class "Default")
      (node (ref "IC33") (pin "14") (pinfunction "A_14") (pintype "input"))
      (node (ref "X1") (pin "B13") (pinfunction "B_B13") (pintype "passive"))
    )
    (net (code "265") (name "REG-LD-ID1") (class "Default")
      (node (ref "IC33") (pin "13") (pinfunction "B_13") (pintype "input"))
      (node (ref "X1") (pin "B14") (pinfunction "B_B14") (pintype "passive"))
    )
    (net (code "266") (name "REG-LD-ID2") (class "Default")
      (node (ref "IC32") (pin "14") (pinfunction "A_14") (pintype "input"))
      (node (ref "X1") (pin "B15") (pinfunction "B_B15") (pintype "passive"))
    )
    (net (code "267") (name "REG-LD-ID3") (class "Default")
      (node (ref "IC32") (pin "13") (pinfunction "B_13") (pintype "input"))
      (node (ref "X1") (pin "B16") (pinfunction "B_B16") (pintype "passive"))
    )
    (net (code "268") (name "REG-RD-ID0") (class "Default")
      (node (ref "IC33") (pin "2") (pinfunction "A_2") (pintype "input"))
      (node (ref "X1") (pin "B9") (pinfunction "B_B9") (pintype "passive"))
    )
    (net (code "269") (name "REG-RD-ID1") (class "Default")
      (node (ref "IC33") (pin "3") (pinfunction "B_3") (pintype "input"))
      (node (ref "X1") (pin "B10") (pinfunction "B_B10") (pintype "passive"))
    )
    (net (code "270") (name "REG-RD-ID2") (class "Default")
      (node (ref "IC32") (pin "2") (pinfunction "A_2") (pintype "input"))
      (node (ref "X1") (pin "B11") (pinfunction "B_B11") (pintype "passive"))
    )
    (net (code "271") (name "REG-RD-ID3") (class "Default")
      (node (ref "IC32") (pin "3") (pinfunction "B_3") (pintype "input"))
      (node (ref "X1") (pin "B12") (pinfunction "B_B12") (pintype "passive"))
    )
    (net (code "272") (name "RESET") (class "Default")
      (node (ref "IC11") (pin "14") (pinfunction "CLR_14") (pintype "input"))
      (node (ref "IC12") (pin "14") (pinfunction "CLR_14") (pintype "input"))
      (node (ref "IC13") (pin "14") (pinfunction "CLR_14") (pintype "input"))
      (node (ref "IC14") (pin "14") (pinfunction "CLR_14") (pintype "input"))
      (node (ref "IC18") (pin "14") (pinfunction "CLR_14") (pintype "input"))
      (node (ref "IC19") (pin "14") (pinfunction "CLR_14") (pintype "input"))
      (node (ref "IC20") (pin "14") (pinfunction "CLR_14") (pintype "input"))
      (node (ref "IC21") (pin "14") (pinfunction "CLR_14") (pintype "input"))
      (node (ref "IC25") (pin "14") (pinfunction "CLR_14") (pintype "input"))
      (node (ref "IC26") (pin "14") (pinfunction "CLR_14") (pintype "input"))
      (node (ref "IC27") (pin "14") (pinfunction "CLR_14") (pintype "input"))
      (node (ref "IC28") (pin "14") (pinfunction "CLR_14") (pintype "input"))
      (node (ref "IC3") (pin "14") (pinfunction "CLR_14") (pintype "input"))
      (node (ref "IC38") (pin "10") (pinfunction "O_10") (pintype "open_collector"))
      (node (ref "IC4") (pin "14") (pinfunction "CLR_14") (pintype "input"))
      (node (ref "IC5") (pin "14") (pinfunction "CLR_14") (pintype "input"))
      (node (ref "IC6") (pin "14") (pinfunction "CLR_14") (pintype "input"))
    )
    (net (code "273") (name "UNUSED0") (class "Default")
      (node (ref "X1") (pin "C12") (pinfunction "B_C12") (pintype "passive"))
    )
    (net (code "274") (name "VCC") (class "Default")
      (node (ref "C1") (pin "1") (pinfunction "1_1") (pintype "passive"))
      (node (ref "C10") (pin "1") (pinfunction "1_1") (pintype "passive"))
      (node (ref "C11") (pin "1") (pinfunction "1_1") (pintype "passive"))
      (node (ref "C12") (pin "1") (pinfunction "1_1") (pintype "passive"))
      (node (ref "C13") (pin "1") (pinfunction "1_1") (pintype "passive"))
      (node (ref "C14") (pin "1") (pinfunction "1_1") (pintype "passive"))
      (node (ref "C15") (pin "1") (pinfunction "1_1") (pintype "passive"))
      (node (ref "C16") (pin "1") (pinfunction "1_1") (pintype "passive"))
      (node (ref "C17") (pin "1") (pinfunction "1_1") (pintype "passive"))
      (node (ref "C18") (pin "1") (pinfunction "1_1") (pintype "passive"))
      (node (ref "C19") (pin "1") (pinfunction "1_1") (pintype "passive"))
      (node (ref "C2") (pin "1") (pinfunction "1_1") (pintype "passive"))
      (node (ref "C20") (pin "1") (pinfunction "1_1") (pintype "passive"))
      (node (ref "C21") (pin "1") (pinfunction "1_1") (pintype "passive"))
      (node (ref "C22") (pin "1") (pinfunction "1_1") (pintype "passive"))
      (node (ref "C23") (pin "1") (pinfunction "1_1") (pintype "passive"))
      (node (ref "C24") (pin "1") (pinfunction "1_1") (pintype "passive"))
      (node (ref "C25") (pin "1") (pinfunction "1_1") (pintype "passive"))
      (node (ref "C26") (pin "1") (pinfunction "1_1") (pintype "passive"))
      (node (ref "C27") (pin "1") (pinfunction "1_1") (pintype "passive"))
      (node (ref "C28") (pin "1") (pinfunction "1_1") (pintype "passive"))
      (node (ref "C29") (pin "1") (pinfunction "1_1") (pintype "passive"))
      (node (ref "C3") (pin "1") (pinfunction "1_1") (pintype "passive"))
      (node (ref "C30") (pin "1") (pinfunction "1_1") (pintype "passive"))
      (node (ref "C31") (pin "1") (pinfunction "1_1") (pintype "passive"))
      (node (ref "C32") (pin "1") (pinfunction "1_1") (pintype "passive"))
      (node (ref "C33") (pin "1") (pinfunction "1_1") (pintype "passive"))
      (node (ref "C34") (pin "1") (pinfunction "1_1") (pintype "passive"))
      (node (ref "C35") (pin "1") (pinfunction "1_1") (pintype "passive"))
      (node (ref "C36") (pin "1") (pinfunction "1_1") (pintype "passive"))
      (node (ref "C37") (pin "1") (pinfunction "1_1") (pintype "passive"))
      (node (ref "C38") (pin "1") (pinfunction "1_1") (pintype "passive"))
      (node (ref "C4") (pin "1") (pinfunction "1_1") (pintype "passive"))
      (node (ref "C5") (pin "1") (pinfunction "1_1") (pintype "passive"))
      (node (ref "C6") (pin "1") (pinfunction "1_1") (pintype "passive"))
      (node (ref "C8") (pin "1") (pinfunction "1_1") (pintype "passive"))
      (node (ref "C9") (pin "1") (pinfunction "1_1") (pintype "passive"))
      (node (ref "R1") (pin "2") (pinfunction "2_2") (pintype "passive"))
      (node (ref "RN1") (pin "1") (pinfunction "1_1") (pintype "passive"))
      (node (ref "RN2") (pin "1") (pinfunction "1_1") (pintype "passive"))
      (node (ref "X1") (pin "A2") (pinfunction "B_A2") (pintype "passive"))
      (node (ref "X1") (pin "A31") (pinfunction "B_A31") (pintype "passive"))
      (node (ref "X1") (pin "B2") (pinfunction "B_B2") (pintype "passive"))
      (node (ref "X1") (pin "B31") (pinfunction "B_B31") (pintype "passive"))
      (node (ref "X1") (pin "C2") (pinfunction "B_C2") (pintype "passive"))
      (node (ref "X1") (pin "C31") (pinfunction "B_C31") (pintype "passive"))
    )
    (net (code "275") (name "unconnected-(IC6A-BO-Pad13)") (class "Default")
      (node (ref "IC6") (pin "13") (pinfunction "BO_13") (pintype "output"))
    )
    (net (code "276") (name "unconnected-(IC6A-CO-Pad12)") (class "Default")
      (node (ref "IC6") (pin "12") (pinfunction "CO_12") (pintype "output"))
    )
    (net (code "277") (name "unconnected-(IC14A-BO-Pad13)") (class "Default")
      (node (ref "IC14") (pin "13") (pinfunction "BO_13") (pintype "output"))
    )
    (net (code "278") (name "unconnected-(IC14A-CO-Pad12)") (class "Default")
      (node (ref "IC14") (pin "12") (pinfunction "CO_12") (pintype "output"))
    )
    (net (code "279") (name "unconnected-(IC21A-BO-Pad13)") (class "Default")
      (node (ref "IC21") (pin "13") (pinfunction "BO_13") (pintype "output"))
    )
    (net (code "280") (name "unconnected-(IC21A-CO-Pad12)") (class "Default")
      (node (ref "IC21") (pin "12") (pinfunction "CO_12") (pintype "output"))
    )
    (net (code "281") (name "unconnected-(IC28A-BO-Pad13)") (class "Default")
      (node (ref "IC28") (pin "13") (pinfunction "BO_13") (pintype "output"))
    )
    (net (code "282") (name "unconnected-(IC28A-CO-Pad12)") (class "Default")
      (node (ref "IC28") (pin "12") (pinfunction "CO_12") (pintype "output"))
    )
    (net (code "283") (name "unconnected-(JP1-Pad3)") (class "Default")
      (node (ref "JP1") (pin "3") (pinfunction "3_3") (pintype "passive"))
    )
    (net (code "284") (name "unconnected-(JP1-Pad4)") (class "Default")
      (node (ref "JP1") (pin "4") (pinfunction "4_4") (pintype "passive"))
    )
    (net (code "285") (name "unconnected-(JP1-Pad37)") (class "Default")
      (node (ref "JP1") (pin "37") (pinfunction "37_37") (pintype "passive"))
    )
    (net (code "286") (name "unconnected-(JP1-Pad38)") (class "Default")
      (node (ref "JP1") (pin "38") (pinfunction "38_38") (pintype "passive"))
    )
    (net (code "287") (name "unconnected-(JP2-Pad3)") (class "Default")
      (node (ref "JP2") (pin "3") (pinfunction "3_3") (pintype "passive"))
    )
    (net (code "288") (name "unconnected-(JP2-Pad4)") (class "Default")
      (node (ref "JP2") (pin "4") (pinfunction "4_4") (pintype "passive"))
    )
    (net (code "289") (name "unconnected-(JP2-Pad37)") (class "Default")
      (node (ref "JP2") (pin "37") (pinfunction "37_37") (pintype "passive"))
    )
    (net (code "290") (name "unconnected-(JP2-Pad38)") (class "Default")
      (node (ref "JP2") (pin "38") (pinfunction "38_38") (pintype "passive"))
    )
  )
)
